# Charger_Control_Board_rev7.net
KiCad netlist of a schematic drawn in EAGLE
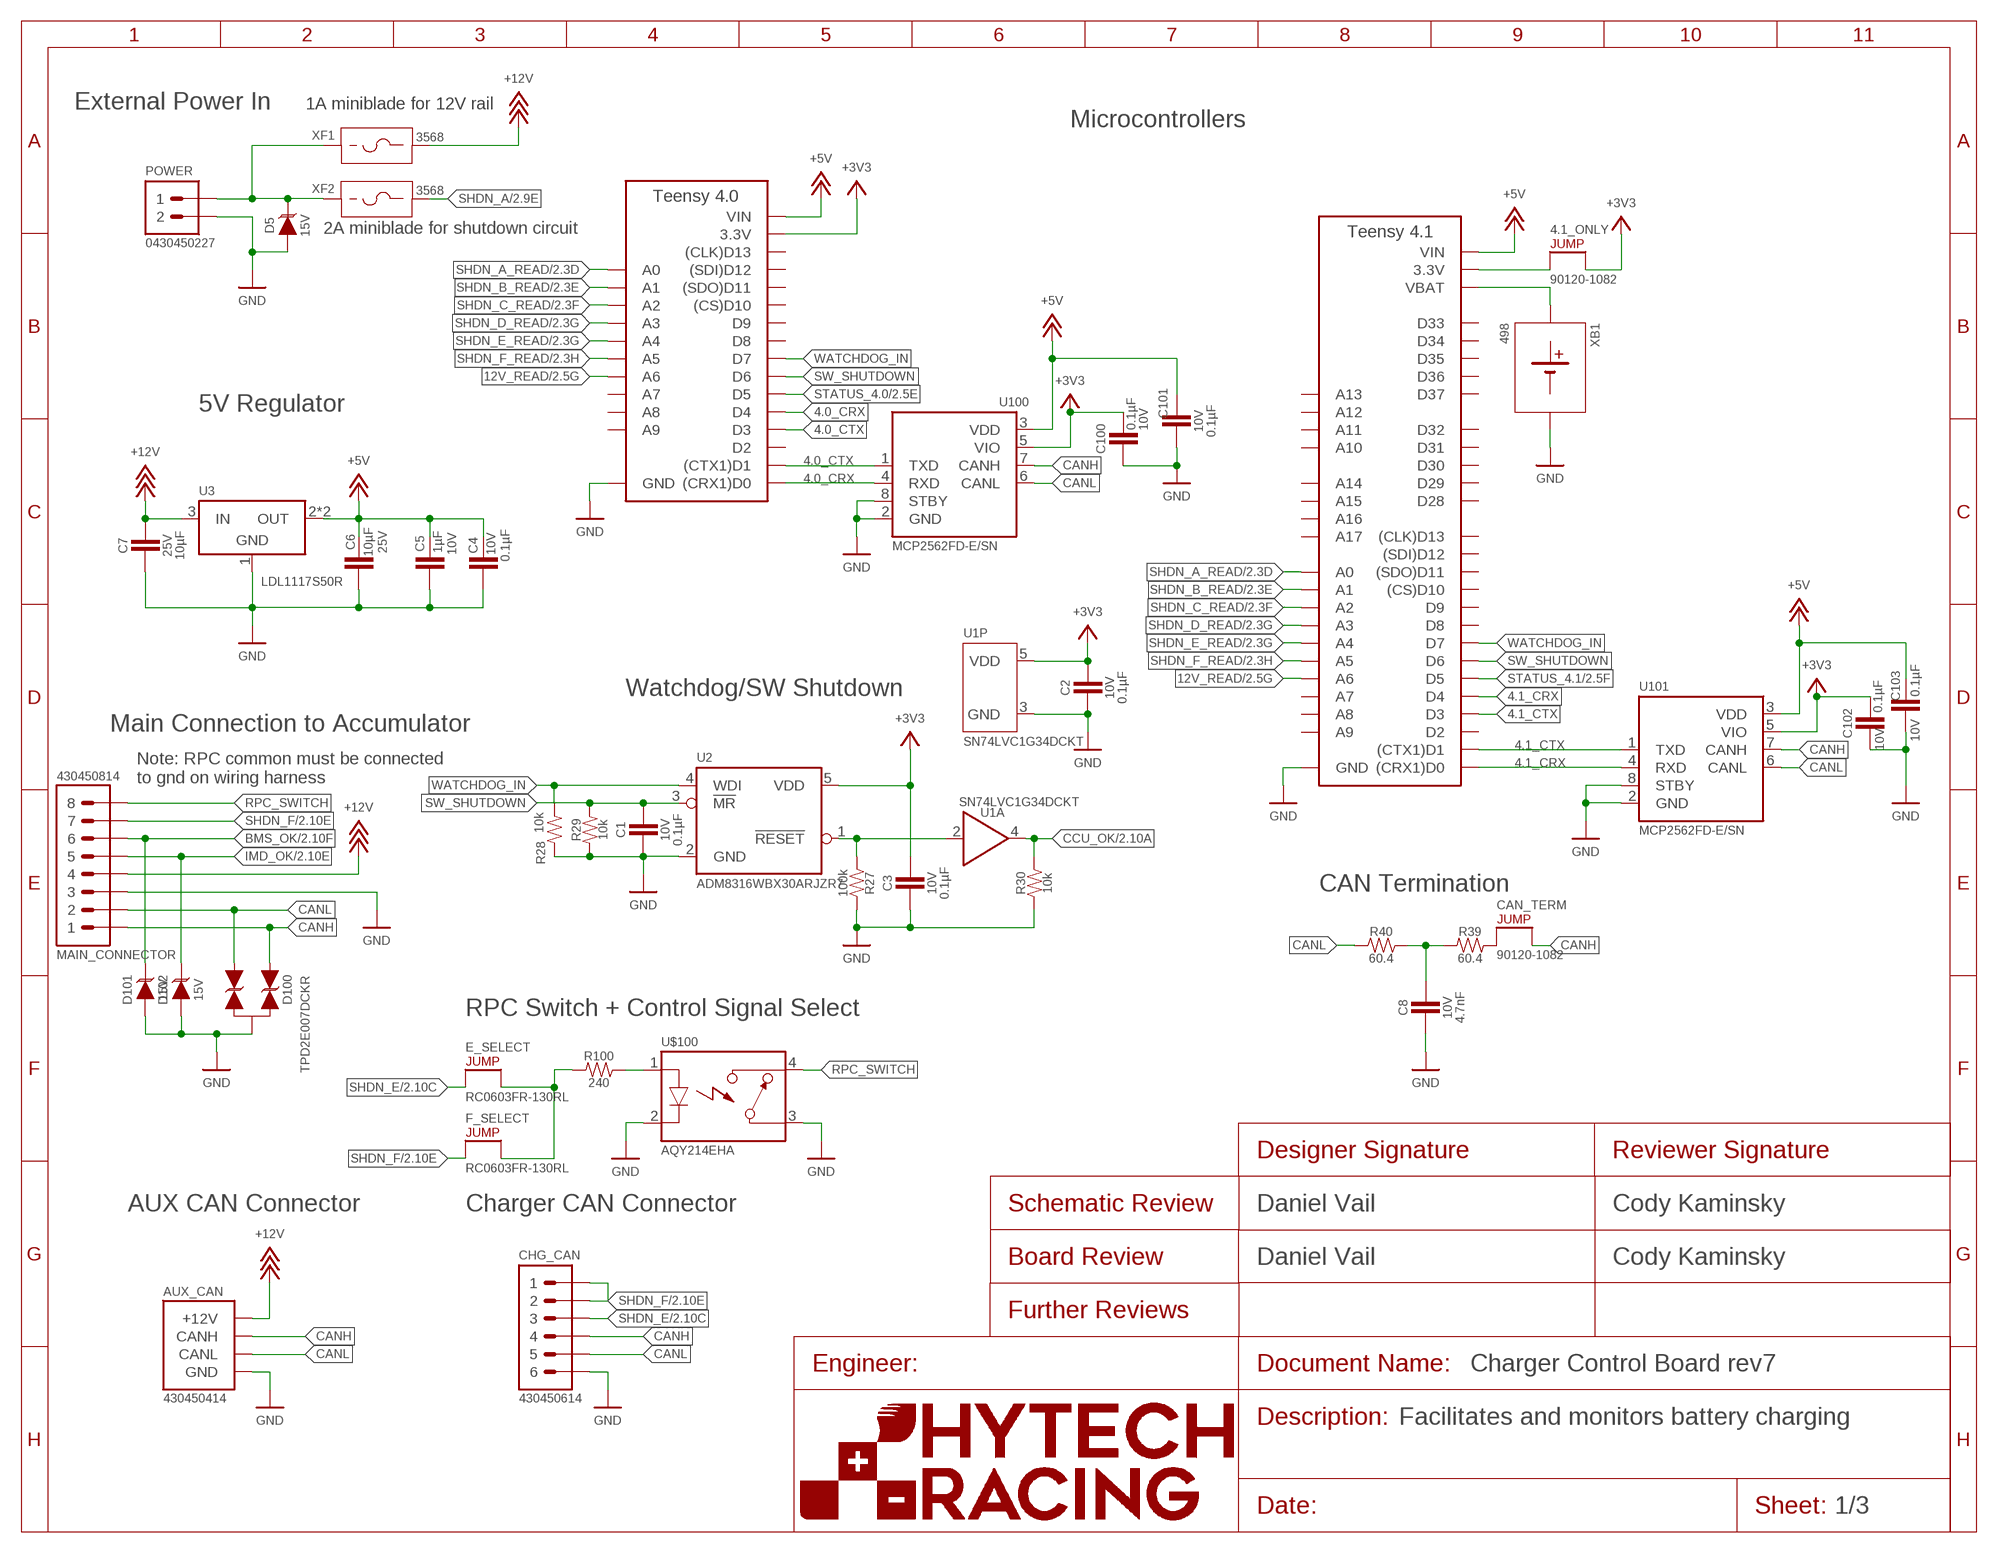
[diagram p0: schematic, sheet 1]
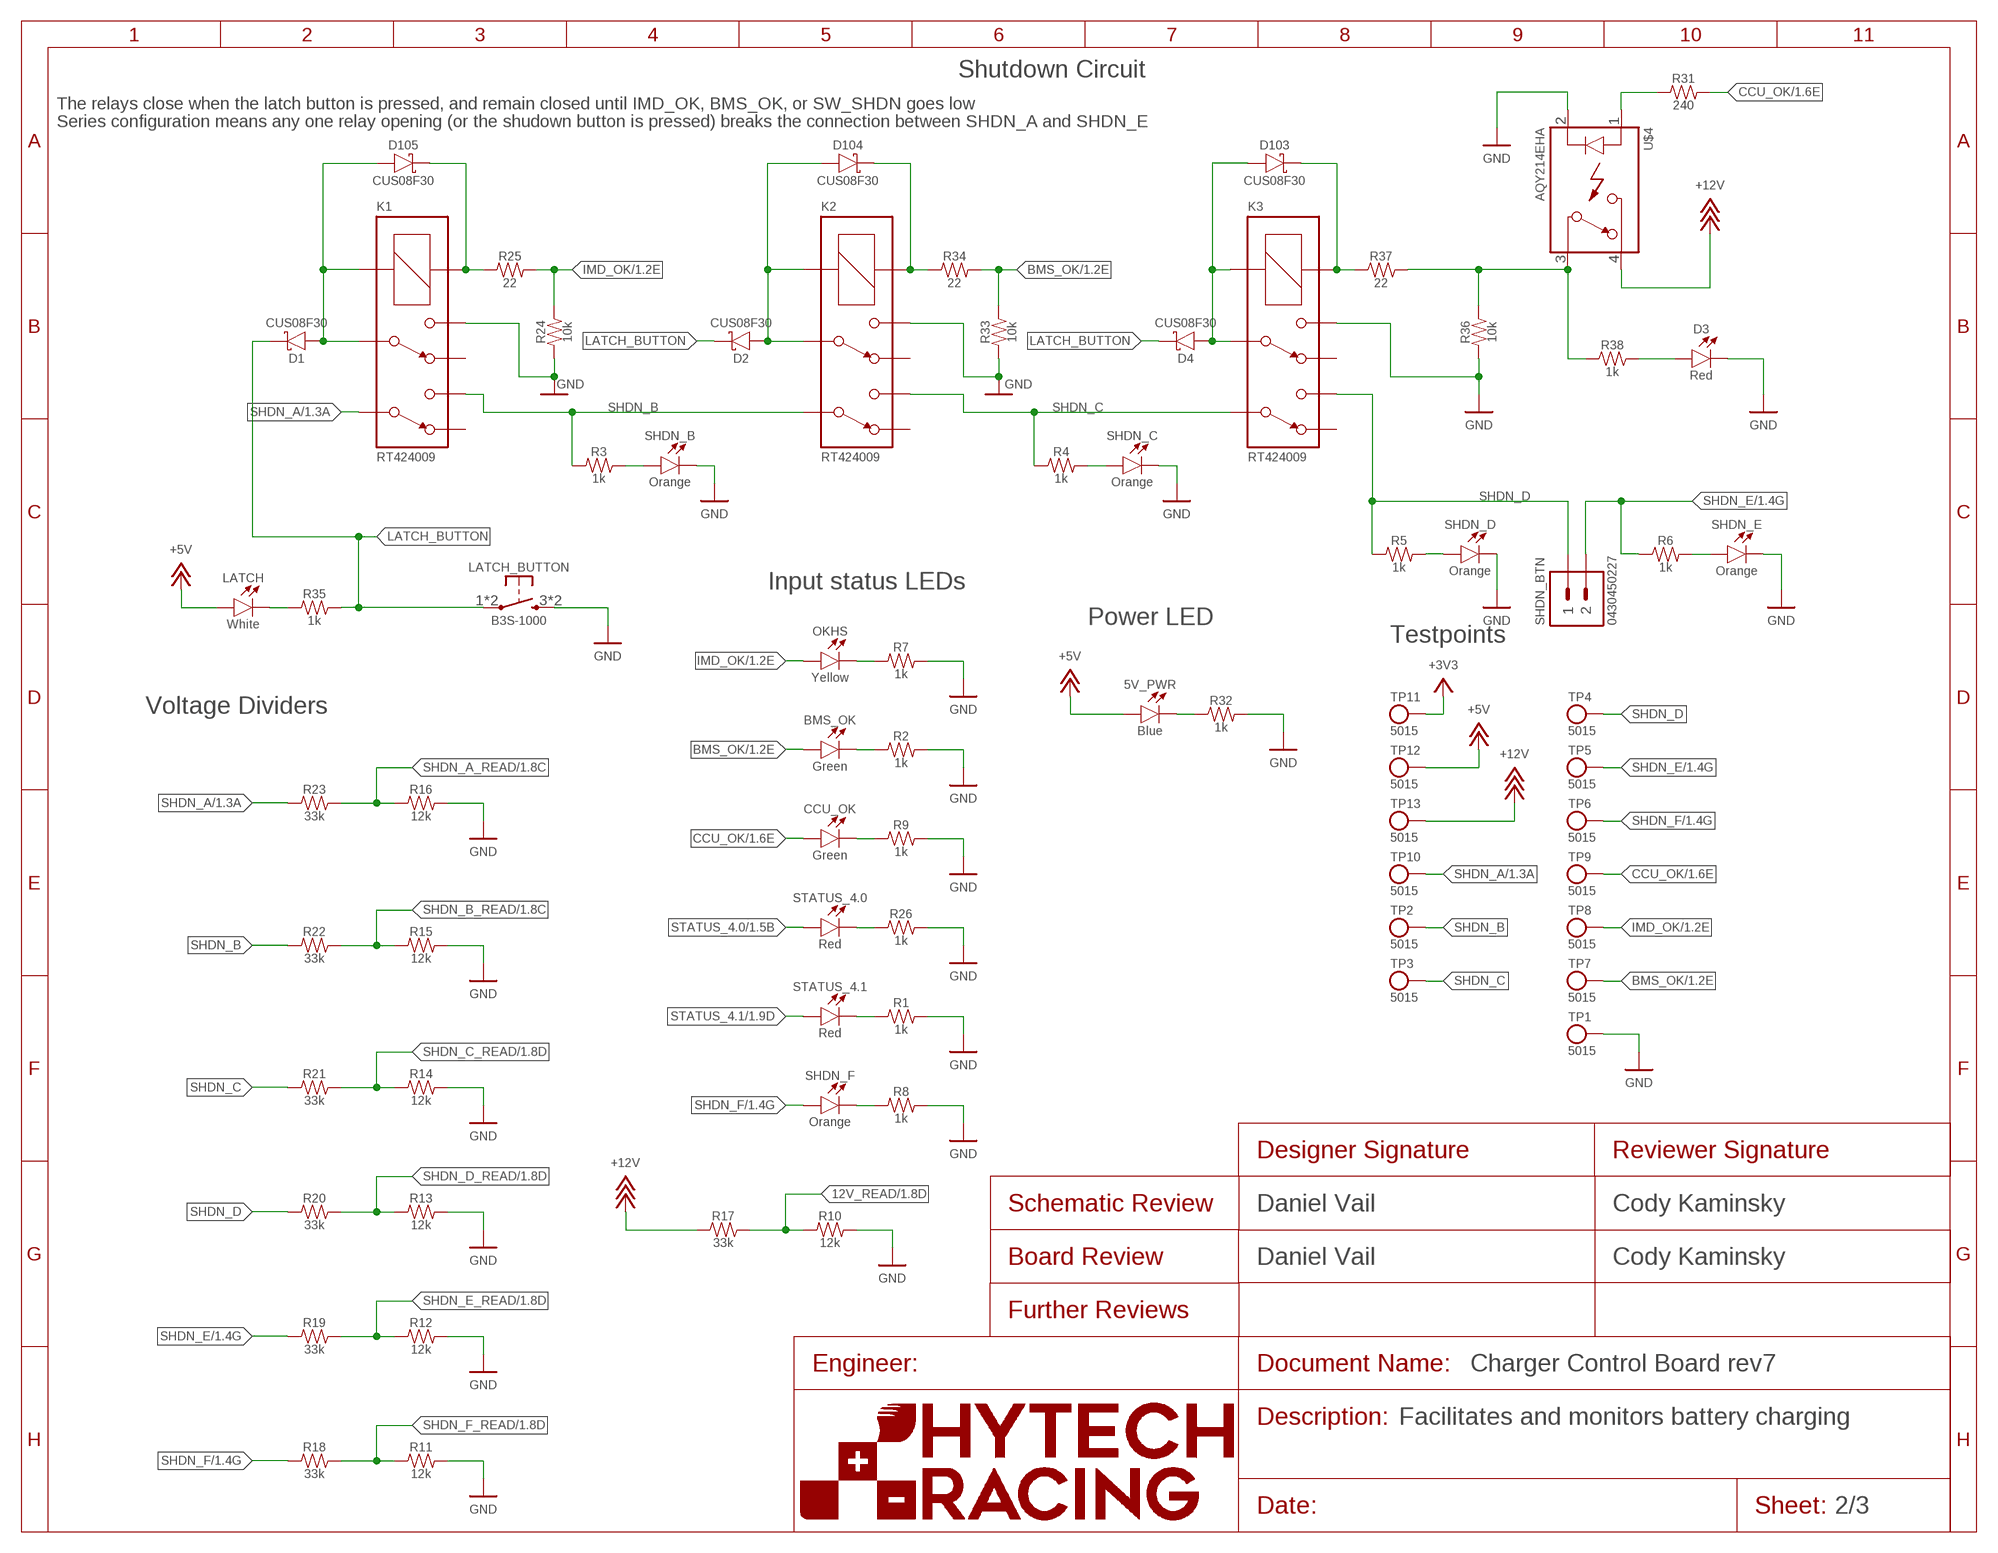
[diagram p1: schematic, sheet 2]
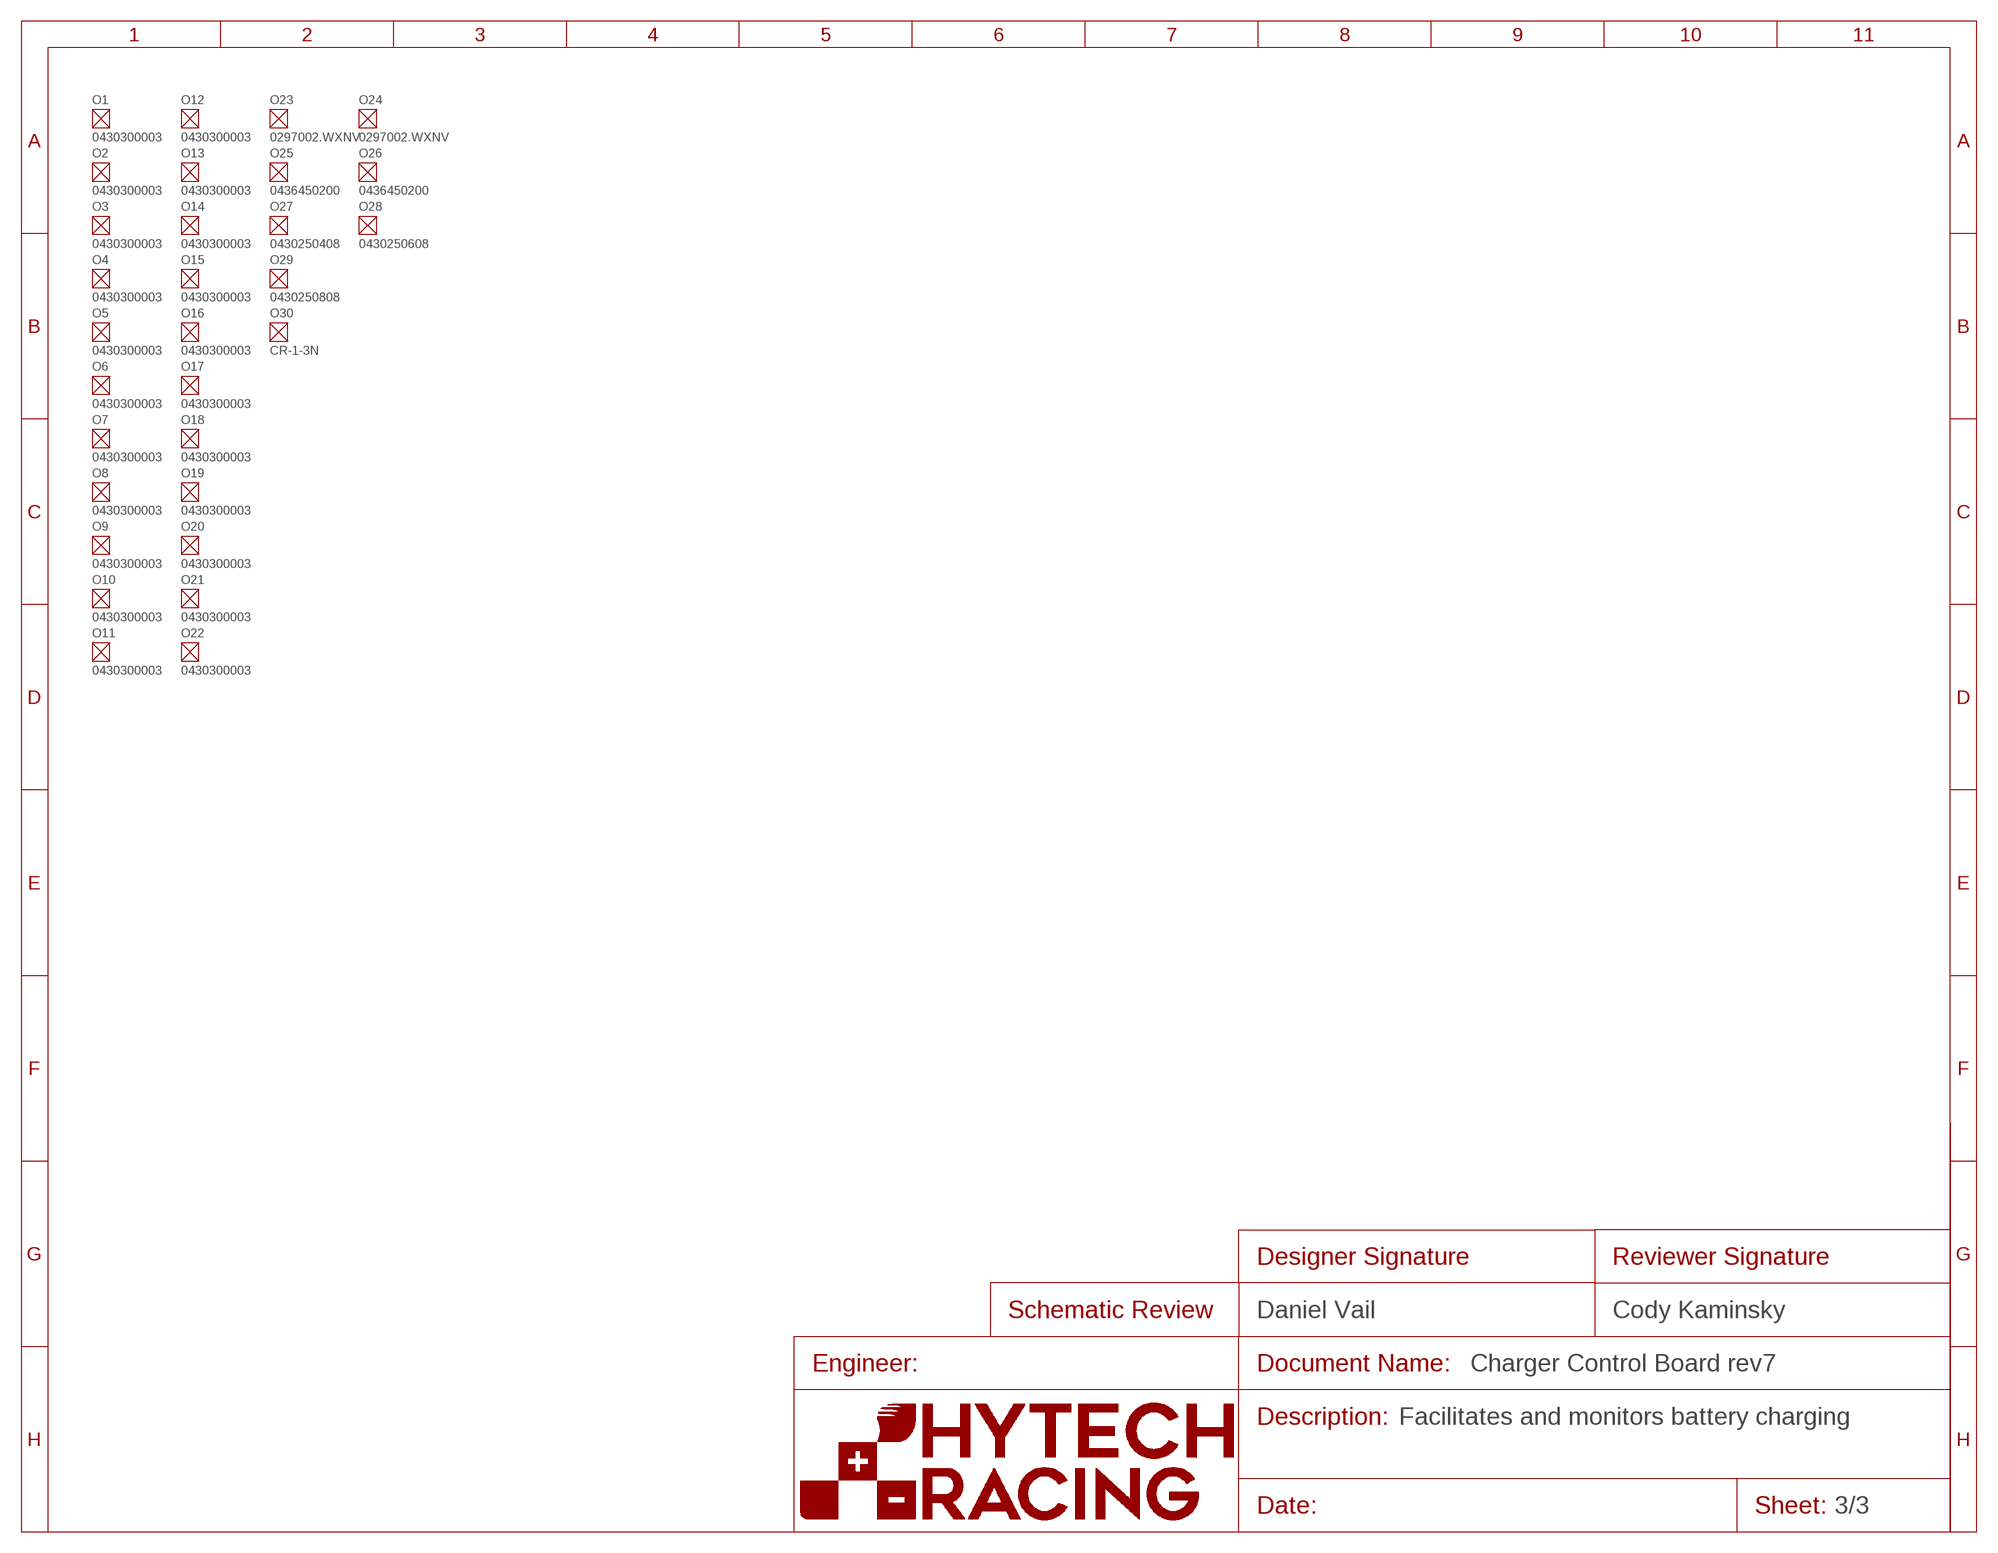
[diagram p2: schematic, sheet 3]

(export (version "E")
  (design (tool "Eeschema 10.0.6"))
  (components
    (comp (ref "5V_PWR")
      (value "LED_0603_BLUE")
      (footprint "eagle-import:0603-LED")
      (fields
        (field (name "COLOR") "Blue")
        (field (name "MANUFACTURER") "Kingbright")
        (field (name "MPN") "APT1608VBC/D")
      )
      (libsource (lib "eagle-import") (part "LED_?_0603BLUE"))
    )
    (comp (ref "BMS_OK")
      (value "LED_0603_GREEN")
      (footprint "eagle-import:0603-LED")
      (fields
        (field (name "COLOR") "Green")
        (field (name "MANUFACTURER") "Kingbright")
        (field (name "MPN") "APT1608ZGCK")
      )
      (libsource (lib "eagle-import") (part "LED_?_0603GREEN"))
    )
    (comp (ref "CCU_OK")
      (value "LED_0603_GREEN")
      (footprint "eagle-import:0603-LED")
      (fields
        (field (name "COLOR") "Green")
        (field (name "MANUFACTURER") "Kingbright")
        (field (name "MPN") "APT1608ZGCK")
      )
      (libsource (lib "eagle-import") (part "LED_?_0603GREEN"))
    )
    (comp (ref "D1")
      (value "SCHOTTKY_SOD323_30V")
      (footprint "eagle-import:SOD-323")
      (fields
        (field (name "MANUFACTURER") "Toshiba Semiconductor and Storage")
        (field (name "MPN") "CUS08F30")
        (field (name "VOLTAGE") "30V")
      )
      (libsource (lib "eagle-import") (part "SCHOTTKY_?_SOD32330V"))
    )
    (comp (ref "D2")
      (value "SCHOTTKY_SOD323_30V")
      (footprint "eagle-import:SOD-323")
      (fields
        (field (name "MANUFACTURER") "Toshiba Semiconductor and Storage")
        (field (name "MPN") "CUS08F30")
        (field (name "VOLTAGE") "30V")
      )
      (libsource (lib "eagle-import") (part "SCHOTTKY_?_SOD32330V"))
    )
    (comp (ref "D3")
      (value "LED_0603_RED")
      (footprint "eagle-import:0603-LED")
      (fields
        (field (name "COLOR") "Red")
        (field (name "MANUFACTURER") "Kingbright")
        (field (name "MPN") "APT1608SECK/J3-PRV")
      )
      (libsource (lib "eagle-import") (part "LED_?_0603RED"))
    )
    (comp (ref "D4")
      (value "SCHOTTKY_SOD323_30V")
      (footprint "eagle-import:SOD-323")
      (fields
        (field (name "MANUFACTURER") "Toshiba Semiconductor and Storage")
        (field (name "MPN") "CUS08F30")
        (field (name "VOLTAGE") "30V")
      )
      (libsource (lib "eagle-import") (part "SCHOTTKY_?_SOD32330V"))
    )
    (comp (ref "D103")
      (value "SCHOTTKY_SOD323_30V")
      (footprint "eagle-import:SOD-323")
      (fields
        (field (name "MANUFACTURER") "Toshiba Semiconductor and Storage")
        (field (name "MPN") "CUS08F30")
        (field (name "VOLTAGE") "30V")
      )
      (libsource (lib "eagle-import") (part "SCHOTTKY_?_SOD32330V"))
    )
    (comp (ref "D104")
      (value "SCHOTTKY_SOD323_30V")
      (footprint "eagle-import:SOD-323")
      (fields
        (field (name "MANUFACTURER") "Toshiba Semiconductor and Storage")
        (field (name "MPN") "CUS08F30")
        (field (name "VOLTAGE") "30V")
      )
      (libsource (lib "eagle-import") (part "SCHOTTKY_?_SOD32330V"))
    )
    (comp (ref "D105")
      (value "SCHOTTKY_SOD323_30V")
      (footprint "eagle-import:SOD-323")
      (fields
        (field (name "MANUFACTURER") "Toshiba Semiconductor and Storage")
        (field (name "MPN") "CUS08F30")
        (field (name "VOLTAGE") "30V")
      )
      (libsource (lib "eagle-import") (part "SCHOTTKY_?_SOD32330V"))
    )
    (comp (ref "K1")
      (value "RELAY_DPDT")
      (footprint "eagle-import:RT_2_")
      (fields (field (name "MPN") "RT424009") (field (name "MANUFACTURER") "TE Connectivity"))
      (libsource (lib "eagle-import") (part "RELAY_DPDT"))
    )
    (comp (ref "K2")
      (value "RELAY_DPDT")
      (footprint "eagle-import:RT_2_")
      (fields (field (name "MPN") "RT424009") (field (name "MANUFACTURER") "TE Connectivity"))
      (libsource (lib "eagle-import") (part "RELAY_DPDT"))
    )
    (comp (ref "K3")
      (value "RELAY_DPDT")
      (footprint "eagle-import:RT_2_")
      (fields (field (name "MPN") "RT424009") (field (name "MANUFACTURER") "TE Connectivity"))
      (libsource (lib "eagle-import") (part "RELAY_DPDT"))
    )
    (comp (ref "LATCH")
      (value "LED_0603_WHITE")
      (footprint "eagle-import:0603-LED")
      (fields
        (field (name "COLOR") "White")
        (field (name "MANUFACTURER") "Bivar Inc.")
        (field (name "MPN") "SM0603UWC")
      )
      (libsource (lib "eagle-import") (part "LED_?_0603WHITE"))
    )
    (comp (ref "LATCH_BUTTON")
      (value "BUTTON")
      (footprint "eagle-import:B3S-100X")
      (fields (field (name "MPN") "B3S-1000") (field (name "MANUFACTURER") "Omron"))
      (libsource (lib "eagle-import") (part "BUTTON"))
    )
    (comp (ref "OKHS")
      (value "LED_0603_YELLOW")
      (footprint "eagle-import:0603-LED")
      (fields
        (field (name "COLOR") "Yellow")
        (field (name "MANUFACTURER") "Kingbright")
        (field (name "MPN") "APT1608SYCK/J3-PRV")
      )
      (libsource (lib "eagle-import") (part "LED_?_0603YELLOW"))
    )
    (comp (ref "R1")
      (value "RESISTOR_0603_1K")
      (footprint "eagle-import:0603-RES")
      (fields
        (field (name "MANUFACTURER") "Yageo")
        (field (name "MPN") "RC0603FR-071KL")
        (field (name "POWER") "0.1W")
        (field (name "RESISTANCE") "1k")
      )
      (libsource (lib "eagle-import") (part "RESISTOR_?_06031K"))
    )
    (comp (ref "R2")
      (value "RESISTOR_0603_1K")
      (footprint "eagle-import:0603-RES")
      (fields
        (field (name "MANUFACTURER") "Yageo")
        (field (name "MPN") "RC0603FR-071KL")
        (field (name "POWER") "0.1W")
        (field (name "RESISTANCE") "1k")
      )
      (libsource (lib "eagle-import") (part "RESISTOR_?_06031K"))
    )
    (comp (ref "R3")
      (value "RESISTOR_0603_1K")
      (footprint "eagle-import:0603-RES")
      (fields
        (field (name "MANUFACTURER") "Yageo")
        (field (name "MPN") "RC0603FR-071KL")
        (field (name "POWER") "0.1W")
        (field (name "RESISTANCE") "1k")
      )
      (libsource (lib "eagle-import") (part "RESISTOR_?_06031K"))
    )
    (comp (ref "R4")
      (value "RESISTOR_0603_1K")
      (footprint "eagle-import:0603-RES")
      (fields
        (field (name "MANUFACTURER") "Yageo")
        (field (name "MPN") "RC0603FR-071KL")
        (field (name "POWER") "0.1W")
        (field (name "RESISTANCE") "1k")
      )
      (libsource (lib "eagle-import") (part "RESISTOR_?_06031K"))
    )
    (comp (ref "R5")
      (value "RESISTOR_0603_1K")
      (footprint "eagle-import:0603-RES")
      (fields
        (field (name "MANUFACTURER") "Yageo")
        (field (name "MPN") "RC0603FR-071KL")
        (field (name "POWER") "0.1W")
        (field (name "RESISTANCE") "1k")
      )
      (libsource (lib "eagle-import") (part "RESISTOR_?_06031K"))
    )
    (comp (ref "R6")
      (value "RESISTOR_0603_1K")
      (footprint "eagle-import:0603-RES")
      (fields
        (field (name "MANUFACTURER") "Yageo")
        (field (name "MPN") "RC0603FR-071KL")
        (field (name "POWER") "0.1W")
        (field (name "RESISTANCE") "1k")
      )
      (libsource (lib "eagle-import") (part "RESISTOR_?_06031K"))
    )
    (comp (ref "R7")
      (value "RESISTOR_0603_1K")
      (footprint "eagle-import:0603-RES")
      (fields
        (field (name "MANUFACTURER") "Yageo")
        (field (name "MPN") "RC0603FR-071KL")
        (field (name "POWER") "0.1W")
        (field (name "RESISTANCE") "1k")
      )
      (libsource (lib "eagle-import") (part "RESISTOR_?_06031K"))
    )
    (comp (ref "R8")
      (value "RESISTOR_0603_1K")
      (footprint "eagle-import:0603-RES")
      (fields
        (field (name "MANUFACTURER") "Yageo")
        (field (name "MPN") "RC0603FR-071KL")
        (field (name "POWER") "0.1W")
        (field (name "RESISTANCE") "1k")
      )
      (libsource (lib "eagle-import") (part "RESISTOR_?_06031K"))
    )
    (comp (ref "R9")
      (value "RESISTOR_0603_1K")
      (footprint "eagle-import:0603-RES")
      (fields
        (field (name "MANUFACTURER") "Yageo")
        (field (name "MPN") "RC0603FR-071KL")
        (field (name "POWER") "0.1W")
        (field (name "RESISTANCE") "1k")
      )
      (libsource (lib "eagle-import") (part "RESISTOR_?_06031K"))
    )
    (comp (ref "R10")
      (value "RESISTOR_0603_12K")
      (footprint "eagle-import:0603-RES")
      (fields
        (field (name "MANUFACTURER") "Yageo")
        (field (name "MPN") "RC0603FR-0712KL")
        (field (name "POWER") "0.1W")
        (field (name "RESISTANCE") "12k")
      )
      (libsource (lib "eagle-import") (part "RESISTOR_?_060312K"))
    )
    (comp (ref "R11")
      (value "RESISTOR_0603_12K")
      (footprint "eagle-import:0603-RES")
      (fields
        (field (name "MANUFACTURER") "Yageo")
        (field (name "MPN") "RC0603FR-0712KL")
        (field (name "POWER") "0.1W")
        (field (name "RESISTANCE") "12k")
      )
      (libsource (lib "eagle-import") (part "RESISTOR_?_060312K"))
    )
    (comp (ref "R12")
      (value "RESISTOR_0603_12K")
      (footprint "eagle-import:0603-RES")
      (fields
        (field (name "MANUFACTURER") "Yageo")
        (field (name "MPN") "RC0603FR-0712KL")
        (field (name "POWER") "0.1W")
        (field (name "RESISTANCE") "12k")
      )
      (libsource (lib "eagle-import") (part "RESISTOR_?_060312K"))
    )
    (comp (ref "R13")
      (value "RESISTOR_0603_12K")
      (footprint "eagle-import:0603-RES")
      (fields
        (field (name "MANUFACTURER") "Yageo")
        (field (name "MPN") "RC0603FR-0712KL")
        (field (name "POWER") "0.1W")
        (field (name "RESISTANCE") "12k")
      )
      (libsource (lib "eagle-import") (part "RESISTOR_?_060312K"))
    )
    (comp (ref "R14")
      (value "RESISTOR_0603_12K")
      (footprint "eagle-import:0603-RES")
      (fields
        (field (name "MANUFACTURER") "Yageo")
        (field (name "MPN") "RC0603FR-0712KL")
        (field (name "POWER") "0.1W")
        (field (name "RESISTANCE") "12k")
      )
      (libsource (lib "eagle-import") (part "RESISTOR_?_060312K"))
    )
    (comp (ref "R15")
      (value "RESISTOR_0603_12K")
      (footprint "eagle-import:0603-RES")
      (fields
        (field (name "MANUFACTURER") "Yageo")
        (field (name "MPN") "RC0603FR-0712KL")
        (field (name "POWER") "0.1W")
        (field (name "RESISTANCE") "12k")
      )
      (libsource (lib "eagle-import") (part "RESISTOR_?_060312K"))
    )
    (comp (ref "R16")
      (value "RESISTOR_0603_12K")
      (footprint "eagle-import:0603-RES")
      (fields
        (field (name "MANUFACTURER") "Yageo")
        (field (name "MPN") "RC0603FR-0712KL")
        (field (name "POWER") "0.1W")
        (field (name "RESISTANCE") "12k")
      )
      (libsource (lib "eagle-import") (part "RESISTOR_?_060312K"))
    )
    (comp (ref "R17")
      (value "RESISTOR_0603_33K")
      (footprint "eagle-import:0603-RES")
      (fields
        (field (name "MANUFACTURER") "Rohm Semiconductor")
        (field (name "MPN") "KTR03EZPF3302")
        (field (name "POWER") "0.1W")
        (field (name "RESISTANCE") "33k")
      )
      (libsource (lib "eagle-import") (part "RESISTOR_?_060333K"))
    )
    (comp (ref "R18")
      (value "RESISTOR_0603_33K")
      (footprint "eagle-import:0603-RES")
      (fields
        (field (name "MANUFACTURER") "Rohm Semiconductor")
        (field (name "MPN") "KTR03EZPF3302")
        (field (name "POWER") "0.1W")
        (field (name "RESISTANCE") "33k")
      )
      (libsource (lib "eagle-import") (part "RESISTOR_?_060333K"))
    )
    (comp (ref "R19")
      (value "RESISTOR_0603_33K")
      (footprint "eagle-import:0603-RES")
      (fields
        (field (name "MANUFACTURER") "Rohm Semiconductor")
        (field (name "MPN") "KTR03EZPF3302")
        (field (name "POWER") "0.1W")
        (field (name "RESISTANCE") "33k")
      )
      (libsource (lib "eagle-import") (part "RESISTOR_?_060333K"))
    )
    (comp (ref "R20")
      (value "RESISTOR_0603_33K")
      (footprint "eagle-import:0603-RES")
      (fields
        (field (name "MANUFACTURER") "Rohm Semiconductor")
        (field (name "MPN") "KTR03EZPF3302")
        (field (name "POWER") "0.1W")
        (field (name "RESISTANCE") "33k")
      )
      (libsource (lib "eagle-import") (part "RESISTOR_?_060333K"))
    )
    (comp (ref "R21")
      (value "RESISTOR_0603_33K")
      (footprint "eagle-import:0603-RES")
      (fields
        (field (name "MANUFACTURER") "Rohm Semiconductor")
        (field (name "MPN") "KTR03EZPF3302")
        (field (name "POWER") "0.1W")
        (field (name "RESISTANCE") "33k")
      )
      (libsource (lib "eagle-import") (part "RESISTOR_?_060333K"))
    )
    (comp (ref "R22")
      (value "RESISTOR_0603_33K")
      (footprint "eagle-import:0603-RES")
      (fields
        (field (name "MANUFACTURER") "Rohm Semiconductor")
        (field (name "MPN") "KTR03EZPF3302")
        (field (name "POWER") "0.1W")
        (field (name "RESISTANCE") "33k")
      )
      (libsource (lib "eagle-import") (part "RESISTOR_?_060333K"))
    )
    (comp (ref "R23")
      (value "RESISTOR_0603_33K")
      (footprint "eagle-import:0603-RES")
      (fields
        (field (name "MANUFACTURER") "Rohm Semiconductor")
        (field (name "MPN") "KTR03EZPF3302")
        (field (name "POWER") "0.1W")
        (field (name "RESISTANCE") "33k")
      )
      (libsource (lib "eagle-import") (part "RESISTOR_?_060333K"))
    )
    (comp (ref "R24")
      (value "RESISTOR_0603_10K")
      (footprint "eagle-import:0603-RES")
      (fields
        (field (name "MANUFACTURER") "Yageo")
        (field (name "MPN") "RC0603FR-0710KL")
        (field (name "POWER") "0.1W")
        (field (name "RESISTANCE") "10k")
      )
      (libsource (lib "eagle-import") (part "RESISTOR_?_060310K"))
    )
    (comp (ref "R25")
      (value "RESISTOR_0603_22")
      (footprint "eagle-import:0603-RES")
      (fields
        (field (name "MANUFACTURER") "Yageo")
        (field (name "MPN") "RC0603FR-0722RL")
        (field (name "POWER") "0.1W")
        (field (name "RESISTANCE") "22")
      )
      (libsource (lib "eagle-import") (part "RESISTOR_?_060322"))
    )
    (comp (ref "R26")
      (value "RESISTOR_0603_1K")
      (footprint "eagle-import:0603-RES")
      (fields
        (field (name "MANUFACTURER") "Yageo")
        (field (name "MPN") "RC0603FR-071KL")
        (field (name "POWER") "0.1W")
        (field (name "RESISTANCE") "1k")
      )
      (libsource (lib "eagle-import") (part "RESISTOR_?_06031K"))
    )
    (comp (ref "R31")
      (value "RESISTOR_0603_240")
      (footprint "eagle-import:0603-RES")
      (fields
        (field (name "MANUFACTURER") "Yageo")
        (field (name "MPN") "RC0603FR-07240RL")
        (field (name "POWER") "0.1W")
        (field (name "RESISTANCE") "240")
      )
      (libsource (lib "eagle-import") (part "RESISTOR_?_0603240"))
    )
    (comp (ref "R32")
      (value "RESISTOR_0603_1K")
      (footprint "eagle-import:0603-RES")
      (fields
        (field (name "MANUFACTURER") "Yageo")
        (field (name "MPN") "RC0603FR-071KL")
        (field (name "POWER") "0.1W")
        (field (name "RESISTANCE") "1k")
      )
      (libsource (lib "eagle-import") (part "RESISTOR_?_06031K"))
    )
    (comp (ref "R33")
      (value "RESISTOR_0603_10K")
      (footprint "eagle-import:0603-RES")
      (fields
        (field (name "MANUFACTURER") "Yageo")
        (field (name "MPN") "RC0603FR-0710KL")
        (field (name "POWER") "0.1W")
        (field (name "RESISTANCE") "10k")
      )
      (libsource (lib "eagle-import") (part "RESISTOR_?_060310K"))
    )
    (comp (ref "R34")
      (value "RESISTOR_0603_22")
      (footprint "eagle-import:0603-RES")
      (fields
        (field (name "MANUFACTURER") "Yageo")
        (field (name "MPN") "RC0603FR-0722RL")
        (field (name "POWER") "0.1W")
        (field (name "RESISTANCE") "22")
      )
      (libsource (lib "eagle-import") (part "RESISTOR_?_060322"))
    )
    (comp (ref "R35")
      (value "RESISTOR_0603_1K")
      (footprint "eagle-import:0603-RES")
      (fields
        (field (name "MANUFACTURER") "Yageo")
        (field (name "MPN") "RC0603FR-071KL")
        (field (name "POWER") "0.1W")
        (field (name "RESISTANCE") "1k")
      )
      (libsource (lib "eagle-import") (part "RESISTOR_?_06031K"))
    )
    (comp (ref "R36")
      (value "RESISTOR_0603_10K")
      (footprint "eagle-import:0603-RES")
      (fields
        (field (name "MANUFACTURER") "Yageo")
        (field (name "MPN") "RC0603FR-0710KL")
        (field (name "POWER") "0.1W")
        (field (name "RESISTANCE") "10k")
      )
      (libsource (lib "eagle-import") (part "RESISTOR_?_060310K"))
    )
    (comp (ref "R37")
      (value "RESISTOR_0603_22")
      (footprint "eagle-import:0603-RES")
      (fields
        (field (name "MANUFACTURER") "Yageo")
        (field (name "MPN") "RC0603FR-0722RL")
        (field (name "POWER") "0.1W")
        (field (name "RESISTANCE") "22")
      )
      (libsource (lib "eagle-import") (part "RESISTOR_?_060322"))
    )
    (comp (ref "R38")
      (value "RESISTOR_0603_1K")
      (footprint "eagle-import:0603-RES")
      (fields
        (field (name "MANUFACTURER") "Yageo")
        (field (name "MPN") "RC0603FR-071KL")
        (field (name "POWER") "0.1W")
        (field (name "RESISTANCE") "1k")
      )
      (libsource (lib "eagle-import") (part "RESISTOR_?_06031K"))
    )
    (comp (ref "SHDN_B")
      (value "LED_0603_ORANGE")
      (footprint "eagle-import:0603-LED")
      (fields
        (field (name "COLOR") "Orange")
        (field (name "MANUFACTURER") "Kingbright")
        (field (name "MPN") "APT1608SECK")
      )
      (libsource (lib "eagle-import") (part "LED_?_0603ORANGE"))
    )
    (comp (ref "SHDN_BTN")
      (value "CONNECTOR-2_μF_T_V_")
      (footprint "eagle-import:MOLEX_MICROFIT_PTH_VERTICAL_02_DUAL")
      (fields (field (name "MPN") "0430450227") (field (name "MANUFACTURER") "Molex"))
      (libsource (lib "eagle-import") (part "CONNECTOR-2_?_μF_T_V"))
    )
    (comp (ref "SHDN_C")
      (value "LED_0603_ORANGE")
      (footprint "eagle-import:0603-LED")
      (fields
        (field (name "COLOR") "Orange")
        (field (name "MANUFACTURER") "Kingbright")
        (field (name "MPN") "APT1608SECK")
      )
      (libsource (lib "eagle-import") (part "LED_?_0603ORANGE"))
    )
    (comp (ref "SHDN_D")
      (value "LED_0603_ORANGE")
      (footprint "eagle-import:0603-LED")
      (fields
        (field (name "COLOR") "Orange")
        (field (name "MANUFACTURER") "Kingbright")
        (field (name "MPN") "APT1608SECK")
      )
      (libsource (lib "eagle-import") (part "LED_?_0603ORANGE"))
    )
    (comp (ref "SHDN_E")
      (value "LED_0603_ORANGE")
      (footprint "eagle-import:0603-LED")
      (fields
        (field (name "COLOR") "Orange")
        (field (name "MANUFACTURER") "Kingbright")
        (field (name "MPN") "APT1608SECK")
      )
      (libsource (lib "eagle-import") (part "LED_?_0603ORANGE"))
    )
    (comp (ref "SHDN_F")
      (value "LED_0603_ORANGE")
      (footprint "eagle-import:0603-LED")
      (fields
        (field (name "COLOR") "Orange")
        (field (name "MANUFACTURER") "Kingbright")
        (field (name "MPN") "APT1608SECK")
      )
      (libsource (lib "eagle-import") (part "LED_?_0603ORANGE"))
    )
    (comp (ref "STATUS_4.0")
      (value "LED_0603_RED")
      (footprint "eagle-import:0603-LED")
      (fields
        (field (name "COLOR") "Red")
        (field (name "MANUFACTURER") "Kingbright")
        (field (name "MPN") "APT1608SECK/J3-PRV")
      )
      (libsource (lib "eagle-import") (part "LED_?_0603RED"))
    )
    (comp (ref "STATUS_4.1")
      (value "LED_0603_RED")
      (footprint "eagle-import:0603-LED")
      (fields
        (field (name "COLOR") "Red")
        (field (name "MANUFACTURER") "Kingbright")
        (field (name "MPN") "APT1608SECK/J3-PRV")
      )
      (libsource (lib "eagle-import") (part "LED_?_0603RED"))
    )
    (comp (ref "TP1")
      (value "TEST_POINT")
      (footprint "eagle-import:5015")
      (fields (field (name "MPN") "5015") (field (name "MANUFACTURER") "Keystone Electronics"))
      (libsource (lib "eagle-import") (part "TEST_POINT"))
    )
    (comp (ref "TP2")
      (value "TEST_POINT")
      (footprint "eagle-import:5015")
      (fields (field (name "MPN") "5015") (field (name "MANUFACTURER") "Keystone Electronics"))
      (libsource (lib "eagle-import") (part "TEST_POINT"))
    )
    (comp (ref "TP3")
      (value "TEST_POINT")
      (footprint "eagle-import:5015")
      (fields (field (name "MPN") "5015") (field (name "MANUFACTURER") "Keystone Electronics"))
      (libsource (lib "eagle-import") (part "TEST_POINT"))
    )
    (comp (ref "TP4")
      (value "TEST_POINT")
      (footprint "eagle-import:5015")
      (fields (field (name "MPN") "5015") (field (name "MANUFACTURER") "Keystone Electronics"))
      (libsource (lib "eagle-import") (part "TEST_POINT"))
    )
    (comp (ref "TP5")
      (value "TEST_POINT")
      (footprint "eagle-import:5015")
      (fields (field (name "MPN") "5015") (field (name "MANUFACTURER") "Keystone Electronics"))
      (libsource (lib "eagle-import") (part "TEST_POINT"))
    )
    (comp (ref "TP6")
      (value "TEST_POINT")
      (footprint "eagle-import:5015")
      (fields (field (name "MPN") "5015") (field (name "MANUFACTURER") "Keystone Electronics"))
      (libsource (lib "eagle-import") (part "TEST_POINT"))
    )
    (comp (ref "TP7")
      (value "TEST_POINT")
      (footprint "eagle-import:5015")
      (fields (field (name "MPN") "5015") (field (name "MANUFACTURER") "Keystone Electronics"))
      (libsource (lib "eagle-import") (part "TEST_POINT"))
    )
    (comp (ref "TP8")
      (value "TEST_POINT")
      (footprint "eagle-import:5015")
      (fields (field (name "MPN") "5015") (field (name "MANUFACTURER") "Keystone Electronics"))
      (libsource (lib "eagle-import") (part "TEST_POINT"))
    )
    (comp (ref "TP9")
      (value "TEST_POINT")
      (footprint "eagle-import:5015")
      (fields (field (name "MPN") "5015") (field (name "MANUFACTURER") "Keystone Electronics"))
      (libsource (lib "eagle-import") (part "TEST_POINT"))
    )
    (comp (ref "TP10")
      (value "TEST_POINT")
      (footprint "eagle-import:5015")
      (fields (field (name "MPN") "5015") (field (name "MANUFACTURER") "Keystone Electronics"))
      (libsource (lib "eagle-import") (part "TEST_POINT"))
    )
    (comp (ref "TP11")
      (value "TEST_POINT")
      (footprint "eagle-import:5015")
      (fields (field (name "MPN") "5015") (field (name "MANUFACTURER") "Keystone Electronics"))
      (libsource (lib "eagle-import") (part "TEST_POINT"))
    )
    (comp (ref "TP12")
      (value "TEST_POINT")
      (footprint "eagle-import:5015")
      (fields (field (name "MPN") "5015") (field (name "MANUFACTURER") "Keystone Electronics"))
      (libsource (lib "eagle-import") (part "TEST_POINT"))
    )
    (comp (ref "TP13")
      (value "TEST_POINT")
      (footprint "eagle-import:5015")
      (fields (field (name "MPN") "5015") (field (name "MANUFACTURER") "Keystone Electronics"))
      (libsource (lib "eagle-import") (part "TEST_POINT"))
    )
    (comp (ref "U$4")
      (value "RELAY_SOLIDSTATE_NO")
      (footprint "eagle-import:DIP-4")
      (fields (field (name "MPN") "AQY214EHA") (field (name "MANUFACTURER") "AQY214EHA"))
      (libsource (lib "eagle-import") (part "RELAY_SOLIDSTATE_NO"))
    )
    (comp (ref "4.1_ONLY")
      (value "JUMPER__1X02")
      (footprint "eagle-import:1X02")
      (fields (field (name "MANUFACTURER") "Molex") (field (name "MPN") "90120-1082 "))
      (libsource (lib "eagle-import") (part "JUMPER_?_1X02"))
    )
    (comp (ref "A1")
      (value "TEENSY_4.1")
      (footprint "eagle-import:TEENSY_LONG_EXT")
      (libsource (lib "eagle-import") (part "TEENSY_4.1"))
    )
    (comp (ref "A2")
      (value "TEENSY_4.0")
      (footprint "eagle-import:TEENSY_SHORT")
      (libsource (lib "eagle-import") (part "TEENSY_4.0"))
    )
    (comp (ref "AUX_CAN")
      (value "CONNECTOR-CAN_MF_T_V_")
      (footprint "eagle-import:MOLEX_MICROFIT_PTH_VERTICAL_04_DUAL")
      (fields (field (name "MPN") "430450414") (field (name "MANUFACTURER") "Molex"))
      (libsource (lib "eagle-import") (part "CONNECTOR-CAN_?_MF_T_V"))
    )
    (comp (ref "C1")
      (value "CAPACITOR_0603_10V_0.1UF")
      (footprint "eagle-import:0603-CAP")
      (fields
        (field (name "CAPACITANCE") "0.1µF")
        (field (name "MANUFACTURER") "Vishay Vitramon")
        (field (name "MPN") "VJ0603Y104JXQPW1BC")
        (field (name "TOLERANCE") "5%")
        (field (name "VOLTAGE") "10V")
      )
      (libsource (lib "eagle-import") (part "CAPACITOR_?_060310V_0.1UF"))
    )
    (comp (ref "C2")
      (value "CAPACITOR_0603_10V_0.1UF")
      (footprint "eagle-import:0603-CAP")
      (fields
        (field (name "CAPACITANCE") "0.1µF")
        (field (name "MANUFACTURER") "Vishay Vitramon")
        (field (name "MPN") "VJ0603Y104JXQPW1BC")
        (field (name "TOLERANCE") "5%")
        (field (name "VOLTAGE") "10V")
      )
      (libsource (lib "eagle-import") (part "CAPACITOR_?_060310V_0.1UF"))
    )
    (comp (ref "C3")
      (value "CAPACITOR_0603_10V_0.1UF")
      (footprint "eagle-import:0603-CAP")
      (fields
        (field (name "CAPACITANCE") "0.1µF")
        (field (name "MANUFACTURER") "Vishay Vitramon")
        (field (name "MPN") "VJ0603Y104JXQPW1BC")
        (field (name "TOLERANCE") "5%")
        (field (name "VOLTAGE") "10V")
      )
      (libsource (lib "eagle-import") (part "CAPACITOR_?_060310V_0.1UF"))
    )
    (comp (ref "C4")
      (value "CAPACITOR_0603_10V_0.1UF")
      (footprint "eagle-import:0603-CAP")
      (fields
        (field (name "CAPACITANCE") "0.1µF")
        (field (name "MANUFACTURER") "Vishay Vitramon")
        (field (name "MPN") "VJ0603Y104JXQPW1BC")
        (field (name "TOLERANCE") "5%")
        (field (name "VOLTAGE") "10V")
      )
      (libsource (lib "eagle-import") (part "CAPACITOR_?_060310V_0.1UF"))
    )
    (comp (ref "C5")
      (value "CAPACITOR_0603_10V_1UF")
      (footprint "eagle-import:0603-CAP")
      (fields
        (field (name "CAPACITANCE") "1µF")
        (field (name "MANUFACTURER") "Yageo")
        (field (name "MPN") "CC0603KRX7R6BB105")
        (field (name "TOLERANCE") "10%")
        (field (name "VOLTAGE") "10V")
      )
      (libsource (lib "eagle-import") (part "CAPACITOR_?_060310V_1UF"))
    )
    (comp (ref "C6")
      (value "CAPACITOR_0603_25V_10UF")
      (footprint "eagle-import:0603-CAP")
      (fields
        (field (name "CAPACITANCE") "10µF")
        (field (name "MANUFACTURER") "Murata Electronics")
        (field (name "MPN") "GRM188R61E106MA73D")
        (field (name "TOLERANCE") "20%")
        (field (name "VOLTAGE") "25V")
      )
      (libsource (lib "eagle-import") (part "CAPACITOR_?_060325V_10UF"))
    )
    (comp (ref "C7")
      (value "CAPACITOR_0603_25V_10UF")
      (footprint "eagle-import:0603-CAP")
      (fields
        (field (name "CAPACITANCE") "10µF")
        (field (name "MANUFACTURER") "Murata Electronics")
        (field (name "MPN") "GRM188R61E106MA73D")
        (field (name "TOLERANCE") "20%")
        (field (name "VOLTAGE") "25V")
      )
      (libsource (lib "eagle-import") (part "CAPACITOR_?_060325V_10UF"))
    )
    (comp (ref "C8")
      (value "CAPACITOR_0603_10V_4.7NF")
      (footprint "eagle-import:0603-CAP")
      (fields
        (field (name "CAPACITANCE") "4.7nF")
        (field (name "MANUFACTURER") "Würth Elektronik")
        (field (name "MPN") "885012206012")
        (field (name "TOLERANCE") "10%")
        (field (name "VOLTAGE") "10V")
      )
      (libsource (lib "eagle-import") (part "CAPACITOR_?_060310V_4.7NF"))
    )
    (comp (ref "C100")
      (value "CAPACITOR_0603_10V_0.1UF")
      (footprint "eagle-import:0603-CAP")
      (fields
        (field (name "CAPACITANCE") "0.1µF")
        (field (name "MANUFACTURER") "Vishay Vitramon")
        (field (name "MPN") "VJ0603Y104JXQPW1BC")
        (field (name "TOLERANCE") "5%")
        (field (name "VOLTAGE") "10V")
      )
      (libsource (lib "eagle-import") (part "CAPACITOR_?_060310V_0.1UF"))
    )
    (comp (ref "C101")
      (value "CAPACITOR_0603_10V_0.1UF")
      (footprint "eagle-import:0603-CAP")
      (fields
        (field (name "CAPACITANCE") "0.1µF")
        (field (name "MANUFACTURER") "Vishay Vitramon")
        (field (name "MPN") "VJ0603Y104JXQPW1BC")
        (field (name "TOLERANCE") "5%")
        (field (name "VOLTAGE") "10V")
      )
      (libsource (lib "eagle-import") (part "CAPACITOR_?_060310V_0.1UF"))
    )
    (comp (ref "C102")
      (value "CAPACITOR_0603_10V_0.1UF")
      (footprint "eagle-import:0603-CAP")
      (fields
        (field (name "CAPACITANCE") "0.1µF")
        (field (name "MANUFACTURER") "Vishay Vitramon")
        (field (name "MPN") "VJ0603Y104JXQPW1BC")
        (field (name "TOLERANCE") "5%")
        (field (name "VOLTAGE") "10V")
      )
      (libsource (lib "eagle-import") (part "CAPACITOR_?_060310V_0.1UF"))
    )
    (comp (ref "C103")
      (value "CAPACITOR_0603_10V_0.1UF")
      (footprint "eagle-import:0603-CAP")
      (fields
        (field (name "CAPACITANCE") "0.1µF")
        (field (name "MANUFACTURER") "Vishay Vitramon")
        (field (name "MPN") "VJ0603Y104JXQPW1BC")
        (field (name "TOLERANCE") "5%")
        (field (name "VOLTAGE") "10V")
      )
      (libsource (lib "eagle-import") (part "CAPACITOR_?_060310V_0.1UF"))
    )
    (comp (ref "CAN_TERM")
      (value "JUMPER__1X02")
      (footprint "eagle-import:1X02")
      (fields (field (name "MANUFACTURER") "Molex") (field (name "MPN") "90120-1082 "))
      (libsource (lib "eagle-import") (part "JUMPER_?_1X02"))
    )
    (comp (ref "CHG_CAN")
      (value "CONNECTOR-6_MF_T_V_")
      (footprint "eagle-import:MOLEX_MICROFIT_PTH_VERTICAL_06_DUAL")
      (fields (field (name "MPN") "430450614") (field (name "MANUFACTURER") "MOLEX"))
      (libsource (lib "eagle-import") (part "CONNECTOR-6_?_MF_T_V"))
    )
    (comp (ref "D5")
      (value "TVS_15V")
      (footprint "eagle-import:SOT-23")
      (fields
        (field (name "MANUFACTURER") "Vishay General Semiconductor - Diodes Division")
        (field (name "MPN") "GSOT15-E3-08")
        (field (name "VOLTAGE") "15V")
      )
      (libsource (lib "eagle-import") (part "TVS_15V"))
    )
    (comp (ref "D100")
      (value "TVS_BIDIRECTIONAL_DUAL")
      (footprint "eagle-import:SC-70-3")
      (fields (field (name "MPN") "TPD2E007DCKR") (field (name "MANUFACTURER") "Texas Instruments"))
      (libsource (lib "eagle-import") (part "TVS_BIDIRECTIONAL_DUAL"))
    )
    (comp (ref "D101")
      (value "TVS_15V")
      (footprint "eagle-import:SOT-23")
      (fields
        (field (name "MANUFACTURER") "Vishay General Semiconductor - Diodes Division")
        (field (name "MPN") "GSOT15-E3-08")
        (field (name "VOLTAGE") "15V")
      )
      (libsource (lib "eagle-import") (part "TVS_15V"))
    )
    (comp (ref "D102")
      (value "TVS_15V")
      (footprint "eagle-import:SOT-23")
      (fields
        (field (name "MANUFACTURER") "Vishay General Semiconductor - Diodes Division")
        (field (name "MPN") "GSOT15-E3-08")
        (field (name "VOLTAGE") "15V")
      )
      (libsource (lib "eagle-import") (part "TVS_15V"))
    )
    (comp (ref "E_SELECT")
      (value "JUMPER_0603_")
      (footprint "eagle-import:0603-RES")
      (fields (field (name "MPN") "RC0603FR-130RL") (field (name "MANUFACTURER") "YAGEO"))
      (libsource (lib "eagle-import") (part "JUMPER_?_0603"))
    )
    (comp (ref "F_SELECT")
      (value "JUMPER_0603_")
      (footprint "eagle-import:0603-RES")
      (fields (field (name "MPN") "RC0603FR-130RL") (field (name "MANUFACTURER") "YAGEO"))
      (libsource (lib "eagle-import") (part "JUMPER_?_0603"))
    )
    (comp (ref "MAIN_CONNECTOR")
      (value "CONNECTOR-8_MF_T_V_")
      (footprint "eagle-import:MOLEX_MICROFIT_PTH_VERTICAL_08_DUAL")
      (fields (field (name "MPN") "430450814") (field (name "MANUFACTURER") "MOLEX"))
      (libsource (lib "eagle-import") (part "CONNECTOR-8_?_MF_T_V"))
    )
    (comp (ref "POWER")
      (value "CONNECTOR-2_μF_T_V_")
      (footprint "eagle-import:MOLEX_MICROFIT_PTH_VERTICAL_02_DUAL")
      (fields (field (name "MPN") "0430450227") (field (name "MANUFACTURER") "Molex"))
      (libsource (lib "eagle-import") (part "CONNECTOR-2_?_μF_T_V"))
    )
    (comp (ref "R27")
      (value "RESISTOR_0603_100K")
      (footprint "eagle-import:0603-RES")
      (fields
        (field (name "MANUFACTURER") "Yageo")
        (field (name "MPN") "RC0603FR-07100KL")
        (field (name "POWER") "0.1W")
        (field (name "RESISTANCE") "100k")
      )
      (libsource (lib "eagle-import") (part "RESISTOR_?_0603100K"))
    )
    (comp (ref "R28")
      (value "RESISTOR_0603_10K")
      (footprint "eagle-import:0603-RES")
      (fields
        (field (name "MANUFACTURER") "Yageo")
        (field (name "MPN") "RC0603FR-0710KL")
        (field (name "POWER") "0.1W")
        (field (name "RESISTANCE") "10k")
      )
      (libsource (lib "eagle-import") (part "RESISTOR_?_060310K"))
    )
    (comp (ref "R29")
      (value "RESISTOR_0603_10K")
      (footprint "eagle-import:0603-RES")
      (fields
        (field (name "MANUFACTURER") "Yageo")
        (field (name "MPN") "RC0603FR-0710KL")
        (field (name "POWER") "0.1W")
        (field (name "RESISTANCE") "10k")
      )
      (libsource (lib "eagle-import") (part "RESISTOR_?_060310K"))
    )
    (comp (ref "R30")
      (value "RESISTOR_0603_10K")
      (footprint "eagle-import:0603-RES")
      (fields
        (field (name "MANUFACTURER") "Yageo")
        (field (name "MPN") "RC0603FR-0710KL")
        (field (name "POWER") "0.1W")
        (field (name "RESISTANCE") "10k")
      )
      (libsource (lib "eagle-import") (part "RESISTOR_?_060310K"))
    )
    (comp (ref "R39")
      (value "RESISTOR_0603_60.4")
      (footprint "eagle-import:0603-RES")
      (fields
        (field (name "MANUFACTURER") "Yageo")
        (field (name "MPN") "RC0603FR-0760R4L")
        (field (name "POWER") "0.1W")
        (field (name "RESISTANCE") "60.4")
      )
      (libsource (lib "eagle-import") (part "RESISTOR_?_060360.4"))
    )
    (comp (ref "R40")
      (value "RESISTOR_0603_60.4")
      (footprint "eagle-import:0603-RES")
      (fields
        (field (name "MANUFACTURER") "Yageo")
        (field (name "MPN") "RC0603FR-0760R4L")
        (field (name "POWER") "0.1W")
        (field (name "RESISTANCE") "60.4")
      )
      (libsource (lib "eagle-import") (part "RESISTOR_?_060360.4"))
    )
    (comp (ref "R100")
      (value "RESISTOR_0603_240")
      (footprint "eagle-import:0603-RES")
      (fields
        (field (name "MANUFACTURER") "Yageo")
        (field (name "MPN") "RC0603FR-07240RL")
        (field (name "POWER") "0.1W")
        (field (name "RESISTANCE") "240")
      )
      (libsource (lib "eagle-import") (part "HyTechDevices_Jumper_RESISTOR_?_0603240"))
    )
    (comp (ref "U$100")
      (value "RELAY_SOLIDSTATE_NO")
      (footprint "eagle-import:DIP-4")
      (fields (field (name "MPN") "AQY214EHA") (field (name "MANUFACTURER") "AQY214EHA"))
      (libsource (lib "eagle-import") (part "RELAY_SOLIDSTATE_NO"))
    )
    (comp (ref "U1")
      (value "LOGICGATE_BUFFER")
      (footprint "eagle-import:SC-70-5")
      (fields (field (name "MANUFACTURER") "Texas Instruments"))
      (libsource (lib "eagle-import") (part "LOGICGATE_BUFFER"))
    )
    (comp (ref "U2")
      (value "ADM8316WBX30")
      (footprint "eagle-import:SOT-23-5")
      (fields (field (name "MANUFACTURER") "Analog Devices Inc.") (field (name "MPN") "ADM8316WBX30ARJZR7"))
      (libsource (lib "eagle-import") (part "ADM8316WBX30"))
    )
    (comp (ref "U3")
      (value "VOLTAGE_REGULATOR_SOT-223_5V")
      (footprint "eagle-import:SOT-223")
      (fields (field (name "MANUFACTURER") "STMicroelectronics") (field (name "MPN") "LDL1117S50R"))
      (libsource (lib "eagle-import") (part "VOLTAGE_REGULATOR_?_SOT-2235V"))
    )
    (comp (ref "U100")
      (value "MCP2562FD")
      (footprint "eagle-import:SOIC-08(NARROW,0.15_)")
      (fields (field (name "MPN") "MCP2562FD-E/SN") (field (name "MANUFACTURER") "Microchip Technology"))
      (libsource (lib "eagle-import") (part "MCP2562FD"))
    )
    (comp (ref "U101")
      (value "MCP2562FD")
      (footprint "eagle-import:SOIC-08(NARROW,0.15_)")
      (fields (field (name "MPN") "MCP2562FD-E/SN") (field (name "MANUFACTURER") "Microchip Technology"))
      (libsource (lib "eagle-import") (part "MCP2562FD"))
    )
    (comp (ref "XB1")
      (value "BATTERY_HOLDER_KEYSTONE_498")
      (footprint "eagle-import:498")
      (fields (field (name "MPN") "498") (field (name "MANUFACTURER") "Keystone Electronics"))
      (libsource (lib "eagle-import") (part "BATTERY_HOLDER_KEYSTONE_498"))
    )
    (comp (ref "XF1")
      (value "FUSE_HOLDER_MINIBLADEPTH")
      (footprint "eagle-import:3568")
      (fields (field (name "MANUFACTURER") "Keystone") (field (name "MPN") "3568"))
      (libsource (lib "eagle-import") (part "FUSE_HOLDER_PTHMINIBLADE"))
    )
    (comp (ref "XF2")
      (value "FUSE_HOLDER_MINIBLADEPTH")
      (footprint "eagle-import:3568")
      (fields (field (name "MANUFACTURER") "Keystone") (field (name "MPN") "3568"))
      (libsource (lib "eagle-import") (part "FUSE_HOLDER_PTHMINIBLADE"))
    )
  )
  (nets
    (net (code "1") (name "+5V") (class "Default")
      (node (ref "5V_PWR") (pin "2") (pinfunction "A_2") (pintype "passive"))
      (node (ref "A1") (pin "VIN") (pinfunction "VIN_VIN") (pintype "power_in"))
      (node (ref "A2") (pin "VIN") (pinfunction "VIN_VIN") (pintype "power_in"))
      (node (ref "C101") (pin "2") (pinfunction "2_2") (pintype "passive"))
      (node (ref "C103") (pin "2") (pinfunction "2_2") (pintype "passive"))
      (node (ref "C4") (pin "2") (pinfunction "2_2") (pintype "passive"))
      (node (ref "C5") (pin "1") (pinfunction "1_1") (pintype "passive"))
      (node (ref "C6") (pin "1") (pinfunction "1_1") (pintype "passive"))
      (node (ref "LATCH") (pin "2") (pinfunction "A_2") (pintype "passive"))
      (node (ref "TP12") (pin "1") (pinfunction "1_1") (pintype "passive"))
      (node (ref "U100") (pin "3") (pinfunction "VDD_3") (pintype "power_in"))
      (node (ref "U101") (pin "3") (pinfunction "VDD_3") (pintype "power_in"))
      (node (ref "U3") (pin "2") (pinfunction "OUT_2") (pintype "power_in"))
      (node (ref "U3") (pin "4") (pinfunction "OUT_4") (pintype "power_in"))
    )
    (net (code "2") (name "+12V") (class "Default")
      (node (ref "AUX_CAN") (pin "1") (pinfunction "+12V_1") (pintype "power_in"))
      (node (ref "C7") (pin "1") (pinfunction "1_1") (pintype "passive"))
      (node (ref "MAIN_CONNECTOR") (pin "4") (pinfunction "4_4") (pintype "passive"))
      (node (ref "R17") (pin "1") (pinfunction "1_1") (pintype "passive"))
      (node (ref "TP13") (pin "1") (pinfunction "1_1") (pintype "passive"))
      (node (ref "U$4") (pin "4") (pinfunction "CONTACT2_4") (pintype "bidirectional"))
      (node (ref "U3") (pin "3") (pinfunction "IN_3") (pintype "power_in"))
      (node (ref "XF1") (pin "3") (pinfunction "2_3") (pintype "passive"))
      (node (ref "XF1") (pin "4") (pinfunction "2_4") (pintype "passive"))
    )
    (net (code "3") (name "4.0_CRX") (class "Default")
      (node (ref "A2") (pin "D0") (pinfunction "(CRX1)D0_D0") (pintype "bidirectional"))
      (node (ref "A2") (pin "D4") (pinfunction "D4_D4") (pintype "bidirectional"))
      (node (ref "U100") (pin "4") (pinfunction "RXD_4") (pintype "output"))
    )
    (net (code "4") (name "4.0_CTX") (class "Default")
      (node (ref "A2") (pin "D1") (pinfunction "(CTX1)D1_D1") (pintype "bidirectional"))
      (node (ref "A2") (pin "D3") (pinfunction "D3_D3") (pintype "bidirectional"))
      (node (ref "U100") (pin "1") (pinfunction "TXD_1") (pintype "input"))
    )
    (net (code "5") (name "4.1_CRX") (class "Default")
      (node (ref "A1") (pin "D0") (pinfunction "(CRX1)D0_D0") (pintype "bidirectional"))
      (node (ref "A1") (pin "D4") (pinfunction "D4_D4") (pintype "bidirectional"))
      (node (ref "U101") (pin "4") (pinfunction "RXD_4") (pintype "output"))
    )
    (net (code "6") (name "4.1_CTX") (class "Default")
      (node (ref "A1") (pin "D1") (pinfunction "(CTX1)D1_D1") (pintype "bidirectional"))
      (node (ref "A1") (pin "D3") (pinfunction "D3_D3") (pintype "bidirectional"))
      (node (ref "U101") (pin "1") (pinfunction "TXD_1") (pintype "input"))
    )
    (net (code "7") (name "12V_READ") (class "Default")
      (node (ref "A1") (pin "D20") (pinfunction "A6_D20") (pintype "bidirectional"))
      (node (ref "A2") (pin "D20") (pinfunction "A6_D20") (pintype "bidirectional"))
      (node (ref "R10") (pin "1") (pinfunction "1_1") (pintype "passive"))
      (node (ref "R17") (pin "2") (pinfunction "2_2") (pintype "passive"))
    )
    (net (code "8") (name "BMS_OK") (class "Default")
      (node (ref "BMS_OK") (pin "2") (pinfunction "A_2") (pintype "passive"))
      (node (ref "D101") (pin "3") (pinfunction "C_3") (pintype "passive"))
      (node (ref "MAIN_CONNECTOR") (pin "6") (pinfunction "6_6") (pintype "passive"))
      (node (ref "R33") (pin "2") (pinfunction "2_2") (pintype "passive"))
      (node (ref "R34") (pin "2") (pinfunction "2_2") (pintype "passive"))
      (node (ref "TP7") (pin "1") (pinfunction "1_1") (pintype "passive"))
    )
    (net (code "9") (name "CANH") (class "Default")
      (node (ref "AUX_CAN") (pin "4") (pinfunction "CANH_4") (pintype "bidirectional"))
      (node (ref "CAN_TERM") (pin "2") (pinfunction "2_2") (pintype "passive"))
      (node (ref "CHG_CAN") (pin "4") (pinfunction "4_4") (pintype "passive"))
      (node (ref "D100") (pin "1") (pinfunction "C1_1") (pintype "passive"))
      (node (ref "MAIN_CONNECTOR") (pin "1") (pinfunction "1_1") (pintype "passive"))
      (node (ref "U100") (pin "7") (pinfunction "CANH_7") (pintype "bidirectional"))
      (node (ref "U101") (pin "7") (pinfunction "CANH_7") (pintype "bidirectional"))
    )
    (net (code "10") (name "CANL") (class "Default")
      (node (ref "AUX_CAN") (pin "3") (pinfunction "CANL_3") (pintype "bidirectional"))
      (node (ref "CHG_CAN") (pin "5") (pinfunction "5_5") (pintype "passive"))
      (node (ref "D100") (pin "2") (pinfunction "C2_2") (pintype "passive"))
      (node (ref "MAIN_CONNECTOR") (pin "2") (pinfunction "2_2") (pintype "passive"))
      (node (ref "R40") (pin "1") (pinfunction "1_1") (pintype "passive"))
      (node (ref "U100") (pin "6") (pinfunction "CANL_6") (pintype "bidirectional"))
      (node (ref "U101") (pin "6") (pinfunction "CANL_6") (pintype "bidirectional"))
    )
    (net (code "11") (name "CCU_OK") (class "Default")
      (node (ref "CCU_OK") (pin "2") (pinfunction "A_2") (pintype "passive"))
      (node (ref "R30") (pin "2") (pinfunction "2_2") (pintype "passive"))
      (node (ref "R31") (pin "2") (pinfunction "2_2") (pintype "passive"))
      (node (ref "TP9") (pin "1") (pinfunction "1_1") (pintype "passive"))
      (node (ref "U1") (pin "4") (pinfunction "OUT_4") (pintype "output"))
    )
    (net (code "12") (name "GND") (class "Default")
      (node (ref "A1") (pin "AGND/GND") (pinfunction "GND_AGND/GND") (pintype "bidirectional"))
      (node (ref "A1") (pin "GND") (pinfunction "GND_GND") (pintype "bidirectional"))
      (node (ref "A1") (pin "GND@2") (pinfunction "GND_GND@2") (pintype "bidirectional"))
      (node (ref "A2") (pin "AGND/GND") (pinfunction "GND_AGND/GND") (pintype "power_in"))
      (node (ref "A2") (pin "GND") (pinfunction "GND_GND") (pintype "power_in"))
      (node (ref "AUX_CAN") (pin "2") (pinfunction "GND_2") (pintype "power_in"))
      (node (ref "C1") (pin "1") (pinfunction "1_1") (pintype "passive"))
      (node (ref "C100") (pin "1") (pinfunction "1_1") (pintype "passive"))
      (node (ref "C101") (pin "1") (pinfunction "1_1") (pintype "passive"))
      (node (ref "C102") (pin "1") (pinfunction "1_1") (pintype "passive"))
      (node (ref "C103") (pin "1") (pinfunction "1_1") (pintype "passive"))
      (node (ref "C2") (pin "1") (pinfunction "1_1") (pintype "passive"))
      (node (ref "C3") (pin "1") (pinfunction "1_1") (pintype "passive"))
      (node (ref "C4") (pin "1") (pinfunction "1_1") (pintype "passive"))
      (node (ref "C5") (pin "2") (pinfunction "2_2") (pintype "passive"))
      (node (ref "C6") (pin "2") (pinfunction "2_2") (pintype "passive"))
      (node (ref "C7") (pin "2") (pinfunction "2_2") (pintype "passive"))
      (node (ref "C8") (pin "2") (pinfunction "2_2") (pintype "passive"))
      (node (ref "CHG_CAN") (pin "6") (pinfunction "6_6") (pintype "passive"))
      (node (ref "D100") (pin "3") (pinfunction "A_3") (pintype "passive"))
      (node (ref "D101") (pin "1") (pinfunction "A_1") (pintype "passive"))
      (node (ref "D102") (pin "1") (pinfunction "A_1") (pintype "passive"))
      (node (ref "D3") (pin "1") (pinfunction "C_1") (pintype "passive"))
      (node (ref "D5") (pin "1") (pinfunction "A_1") (pintype "passive"))
      (node (ref "K1") (pin "14") (pinfunction "4_14") (pintype "bidirectional"))
      (node (ref "K2") (pin "14") (pinfunction "4_14") (pintype "bidirectional"))
      (node (ref "K3") (pin "14") (pinfunction "4_14") (pintype "bidirectional"))
      (node (ref "LATCH_BUTTON") (pin "3") (pinfunction "S_3") (pintype "passive"))
      (node (ref "LATCH_BUTTON") (pin "4") (pinfunction "S_4") (pintype "passive"))
      (node (ref "MAIN_CONNECTOR") (pin "3") (pinfunction "3_3") (pintype "passive"))
      (node (ref "POWER") (pin "2") (pinfunction "2_2") (pintype "passive"))
      (node (ref "R1") (pin "2") (pinfunction "2_2") (pintype "passive"))
      (node (ref "R10") (pin "2") (pinfunction "2_2") (pintype "passive"))
      (node (ref "R11") (pin "2") (pinfunction "2_2") (pintype "passive"))
      (node (ref "R12") (pin "2") (pinfunction "2_2") (pintype "passive"))
      (node (ref "R13") (pin "2") (pinfunction "2_2") (pintype "passive"))
      (node (ref "R14") (pin "2") (pinfunction "2_2") (pintype "passive"))
      (node (ref "R15") (pin "2") (pinfunction "2_2") (pintype "passive"))
      (node (ref "R16") (pin "2") (pinfunction "2_2") (pintype "passive"))
      (node (ref "R2") (pin "2") (pinfunction "2_2") (pintype "passive"))
      (node (ref "R24") (pin "1") (pinfunction "1_1") (pintype "passive"))
      (node (ref "R26") (pin "2") (pinfunction "2_2") (pintype "passive"))
      (node (ref "R27") (pin "2") (pinfunction "2_2") (pintype "passive"))
      (node (ref "R28") (pin "2") (pinfunction "2_2") (pintype "passive"))
      (node (ref "R29") (pin "1") (pinfunction "1_1") (pintype "passive"))
      (node (ref "R30") (pin "1") (pinfunction "1_1") (pintype "passive"))
      (node (ref "R32") (pin "2") (pinfunction "2_2") (pintype "passive"))
      (node (ref "R33") (pin "1") (pinfunction "1_1") (pintype "passive"))
      (node (ref "R36") (pin "1") (pinfunction "1_1") (pintype "passive"))
      (node (ref "R7") (pin "2") (pinfunction "2_2") (pintype "passive"))
      (node (ref "R8") (pin "2") (pinfunction "2_2") (pintype "passive"))
      (node (ref "R9") (pin "2") (pinfunction "2_2") (pintype "passive"))
      (node (ref "SHDN_B") (pin "1") (pinfunction "C_1") (pintype "passive"))
      (node (ref "SHDN_C") (pin "1") (pinfunction "C_1") (pintype "passive"))
      (node (ref "SHDN_D") (pin "1") (pinfunction "C_1") (pintype "passive"))
      (node (ref "SHDN_E") (pin "1") (pinfunction "C_1") (pintype "passive"))
      (node (ref "TP1") (pin "1") (pinfunction "1_1") (pintype "passive"))
      (node (ref "U$100") (pin "2") (pinfunction "CONTROL-_2") (pintype "passive"))
      (node (ref "U$100") (pin "3") (pinfunction "CONTACT1_3") (pintype "bidirectional"))
      (node (ref "U$4") (pin "2") (pinfunction "CONTROL-_2") (pintype "passive"))
      (node (ref "U1") (pin "3") (pinfunction "GND_3") (pintype "power_in"))
      (node (ref "U100") (pin "2") (pinfunction "GND_2") (pintype "power_in"))
      (node (ref "U100") (pin "8") (pinfunction "STBY_8") (pintype "passive"))
      (node (ref "U101") (pin "2") (pinfunction "GND_2") (pintype "power_in"))
      (node (ref "U101") (pin "8") (pinfunction "STBY_8") (pintype "passive"))
      (node (ref "U2") (pin "2") (pinfunction "GND_2") (pintype "power_in"))
      (node (ref "U3") (pin "1") (pinfunction "GND_1") (pintype "power_in"))
      (node (ref "XB1") (pin "2") (pinfunction "MINUS_2") (pintype "power_in"))
    )
    (net (code "13") (name "IMD_OK") (class "Default")
      (node (ref "D102") (pin "3") (pinfunction "C_3") (pintype "passive"))
      (node (ref "MAIN_CONNECTOR") (pin "5") (pinfunction "5_5") (pintype "passive"))
      (node (ref "OKHS") (pin "2") (pinfunction "A_2") (pintype "passive"))
      (node (ref "R24") (pin "2") (pinfunction "2_2") (pintype "passive"))
      (node (ref "R25") (pin "2") (pinfunction "2_2") (pintype "passive"))
      (node (ref "TP8") (pin "1") (pinfunction "1_1") (pintype "passive"))
    )
    (net (code "14") (name "LATCH_BUTTON") (class "Default")
      (node (ref "D1") (pin "C") (pinfunction "C_C") (pintype "passive"))
      (node (ref "D2") (pin "C") (pinfunction "C_C") (pintype "passive"))
      (node (ref "D4") (pin "C") (pinfunction "C_C") (pintype "passive"))
      (node (ref "LATCH_BUTTON") (pin "1") (pinfunction "P_1") (pintype "passive"))
      (node (ref "LATCH_BUTTON") (pin "2") (pinfunction "P_2") (pintype "passive"))
      (node (ref "R35") (pin "2") (pinfunction "2_2") (pintype "passive"))
    )
    (net (code "15") (name "Net-(4.1_ONLY-Pad1)") (class "Default")
      (node (ref "4.1_ONLY") (pin "1") (pinfunction "1_1") (pintype "passive"))
      (node (ref "A1") (pin "3V3") (pinfunction "3.3V_3V3") (pintype "power_in"))
      (node (ref "A1") (pin "3V3@2") (pinfunction "3.3V_3V3@2") (pintype "power_in"))
      (node (ref "A1") (pin "3V3@3") (pinfunction "3.3V_3V3@3") (pintype "power_in"))
    )
    (net (code "16") (name "Net-(5V_PWR-C)") (class "Default")
      (node (ref "5V_PWR") (pin "1") (pinfunction "C_1") (pintype "passive"))
      (node (ref "R32") (pin "1") (pinfunction "1_1") (pintype "passive"))
    )
    (net (code "17") (name "Net-(BMS_OK-C)") (class "Default")
      (node (ref "BMS_OK") (pin "1") (pinfunction "C_1") (pintype "passive"))
      (node (ref "R2") (pin "1") (pinfunction "1_1") (pintype "passive"))
    )
    (net (code "18") (name "Net-(C8-Pad1)") (class "Default")
      (node (ref "C8") (pin "1") (pinfunction "1_1") (pintype "passive"))
      (node (ref "R39") (pin "1") (pinfunction "1_1") (pintype "passive"))
      (node (ref "R40") (pin "2") (pinfunction "2_2") (pintype "passive"))
    )
    (net (code "19") (name "Net-(CAN_TERM-Pad1)") (class "Default")
      (node (ref "CAN_TERM") (pin "1") (pinfunction "1_1") (pintype "passive"))
      (node (ref "R39") (pin "2") (pinfunction "2_2") (pintype "passive"))
    )
    (net (code "20") (name "Net-(CCU_OK-C)") (class "Default")
      (node (ref "CCU_OK") (pin "1") (pinfunction "C_1") (pintype "passive"))
      (node (ref "R9") (pin "1") (pinfunction "1_1") (pintype "passive"))
    )
    (net (code "21") (name "Net-(D3-A)") (class "Default")
      (node (ref "D3") (pin "2") (pinfunction "A_2") (pintype "passive"))
      (node (ref "R38") (pin "2") (pinfunction "2_2") (pintype "passive"))
    )
    (net (code "22") (name "Net-(D5-C)") (class "Default")
      (node (ref "D5") (pin "3") (pinfunction "C_3") (pintype "passive"))
      (node (ref "POWER") (pin "1") (pinfunction "1_1") (pintype "passive"))
      (node (ref "XF1") (pin "1") (pinfunction "1_1") (pintype "passive"))
      (node (ref "XF1") (pin "2") (pinfunction "1_2") (pintype "passive"))
      (node (ref "XF2") (pin "1") (pinfunction "1_1") (pintype "passive"))
      (node (ref "XF2") (pin "2") (pinfunction "1_2") (pintype "passive"))
    )
    (net (code "23") (name "Net-(E_SELECT-Pad2)") (class "Default")
      (node (ref "E_SELECT") (pin "2") (pinfunction "2_2") (pintype "passive"))
      (node (ref "F_SELECT") (pin "2") (pinfunction "2_2") (pintype "passive"))
      (node (ref "R100") (pin "1") (pinfunction "1_1") (pintype "passive"))
    )
    (net (code "24") (name "Net-(K1-3)") (class "Default")
      (node (ref "D1") (pin "A") (pinfunction "A_A") (pintype "passive"))
      (node (ref "D105") (pin "A") (pinfunction "A_A") (pintype "passive"))
      (node (ref "K1") (pin "11") (pinfunction "3_11") (pintype "bidirectional"))
      (node (ref "K1") (pin "A2") (pinfunction "COIL-_A2") (pintype "bidirectional"))
    )
    (net (code "25") (name "Net-(K1-COIL+)") (class "Default")
      (node (ref "D105") (pin "C") (pinfunction "C_C") (pintype "passive"))
      (node (ref "K1") (pin "A1") (pinfunction "COIL+_A1") (pintype "bidirectional"))
      (node (ref "R25") (pin "1") (pinfunction "1_1") (pintype "passive"))
    )
    (net (code "26") (name "Net-(K2-3)") (class "Default")
      (node (ref "D104") (pin "A") (pinfunction "A_A") (pintype "passive"))
      (node (ref "D2") (pin "A") (pinfunction "A_A") (pintype "passive"))
      (node (ref "K2") (pin "11") (pinfunction "3_11") (pintype "bidirectional"))
      (node (ref "K2") (pin "A2") (pinfunction "COIL-_A2") (pintype "bidirectional"))
    )
    (net (code "27") (name "Net-(K2-COIL+)") (class "Default")
      (node (ref "D104") (pin "C") (pinfunction "C_C") (pintype "passive"))
      (node (ref "K2") (pin "A1") (pinfunction "COIL+_A1") (pintype "bidirectional"))
      (node (ref "R34") (pin "1") (pinfunction "1_1") (pintype "passive"))
    )
    (net (code "28") (name "Net-(K3-3)") (class "Default")
      (node (ref "D103") (pin "A") (pinfunction "A_A") (pintype "passive"))
      (node (ref "D4") (pin "A") (pinfunction "A_A") (pintype "passive"))
      (node (ref "K3") (pin "11") (pinfunction "3_11") (pintype "bidirectional"))
      (node (ref "K3") (pin "A2") (pinfunction "COIL-_A2") (pintype "bidirectional"))
    )
    (net (code "29") (name "Net-(K3-COIL+)") (class "Default")
      (node (ref "D103") (pin "C") (pinfunction "C_C") (pintype "passive"))
      (node (ref "K3") (pin "A1") (pinfunction "COIL+_A1") (pintype "bidirectional"))
      (node (ref "R37") (pin "1") (pinfunction "1_1") (pintype "passive"))
    )
    (net (code "30") (name "Net-(LATCH-C)") (class "Default")
      (node (ref "LATCH") (pin "1") (pinfunction "C_1") (pintype "passive"))
      (node (ref "R35") (pin "1") (pinfunction "1_1") (pintype "passive"))
    )
    (net (code "31") (name "Net-(OKHS-C)") (class "Default")
      (node (ref "OKHS") (pin "1") (pinfunction "C_1") (pintype "passive"))
      (node (ref "R7") (pin "1") (pinfunction "1_1") (pintype "passive"))
    )
    (net (code "32") (name "Net-(SHDN_B-A)") (class "Default")
      (node (ref "R3") (pin "2") (pinfunction "2_2") (pintype "passive"))
      (node (ref "SHDN_B") (pin "2") (pinfunction "A_2") (pintype "passive"))
    )
    (net (code "33") (name "Net-(SHDN_C-A)") (class "Default")
      (node (ref "R4") (pin "2") (pinfunction "2_2") (pintype "passive"))
      (node (ref "SHDN_C") (pin "2") (pinfunction "A_2") (pintype "passive"))
    )
    (net (code "34") (name "Net-(SHDN_D-A)") (class "Default")
      (node (ref "R5") (pin "2") (pinfunction "2_2") (pintype "passive"))
      (node (ref "SHDN_D") (pin "2") (pinfunction "A_2") (pintype "passive"))
    )
    (net (code "35") (name "Net-(SHDN_E-A)") (class "Default")
      (node (ref "R6") (pin "2") (pinfunction "2_2") (pintype "passive"))
      (node (ref "SHDN_E") (pin "2") (pinfunction "A_2") (pintype "passive"))
    )
    (net (code "36") (name "Net-(SHDN_F-C)") (class "Default")
      (node (ref "R8") (pin "1") (pinfunction "1_1") (pintype "passive"))
      (node (ref "SHDN_F") (pin "1") (pinfunction "C_1") (pintype "passive"))
    )
    (net (code "37") (name "Net-(STATUS_4.0-C)") (class "Default")
      (node (ref "R26") (pin "1") (pinfunction "1_1") (pintype "passive"))
      (node (ref "STATUS_4.0") (pin "1") (pinfunction "C_1") (pintype "passive"))
    )
    (net (code "38") (name "Net-(STATUS_4.1-C)") (class "Default")
      (node (ref "R1") (pin "1") (pinfunction "1_1") (pintype "passive"))
      (node (ref "STATUS_4.1") (pin "1") (pinfunction "C_1") (pintype "passive"))
    )
    (net (code "39") (name "Net-(U$4-CONTACT1)") (class "Default")
      (node (ref "R36") (pin "2") (pinfunction "2_2") (pintype "passive"))
      (node (ref "R37") (pin "2") (pinfunction "2_2") (pintype "passive"))
      (node (ref "R38") (pin "1") (pinfunction "1_1") (pintype "passive"))
      (node (ref "U$4") (pin "3") (pinfunction "CONTACT1_3") (pintype "bidirectional"))
    )
    (net (code "40") (name "Net-(U$4-CONTROL+)") (class "Default")
      (node (ref "R31") (pin "1") (pinfunction "1_1") (pintype "passive"))
      (node (ref "U$4") (pin "1") (pinfunction "CONTROL+_1") (pintype "passive"))
    )
    (net (code "41") (name "Net-(U$100-CONTROL+)") (class "Default")
      (node (ref "R100") (pin "2") (pinfunction "2_2") (pintype "passive"))
      (node (ref "U$100") (pin "1") (pinfunction "CONTROL+_1") (pintype "passive"))
    )
    (net (code "42") (name "Net-(U1A-IN)") (class "Default")
      (node (ref "R27") (pin "1") (pinfunction "1_1") (pintype "passive"))
      (node (ref "U1") (pin "2") (pinfunction "IN_2") (pintype "input"))
      (node (ref "U2") (pin "1") (pinfunction "~{RESET}_1") (pintype "output"))
    )
    (net (code "43") (name "Net-(XB1-PLUS)") (class "Default")
      (node (ref "A1") (pin "VBAT") (pinfunction "VBAT_VBAT") (pintype "power_in"))
      (node (ref "XB1") (pin "1") (pinfunction "PLUS_1") (pintype "power_in"))
    )
    (net (code "44") (name "RPC_SWITCH") (class "Default")
      (node (ref "MAIN_CONNECTOR") (pin "8") (pinfunction "8_8") (pintype "passive"))
      (node (ref "U$100") (pin "4") (pinfunction "CONTACT2_4") (pintype "bidirectional"))
    )
    (net (code "45") (name "SHDN_A") (class "Default")
      (node (ref "K1") (pin "21") (pinfunction "6_21") (pintype "bidirectional"))
      (node (ref "R23") (pin "1") (pinfunction "1_1") (pintype "passive"))
      (node (ref "TP10") (pin "1") (pinfunction "1_1") (pintype "passive"))
      (node (ref "XF2") (pin "3") (pinfunction "2_3") (pintype "passive"))
      (node (ref "XF2") (pin "4") (pinfunction "2_4") (pintype "passive"))
    )
    (net (code "46") (name "SHDN_A_READ") (class "Default")
      (node (ref "A1") (pin "D14") (pinfunction "A0_D14") (pintype "bidirectional"))
      (node (ref "A2") (pin "D14") (pinfunction "A0_D14") (pintype "bidirectional"))
      (node (ref "R16") (pin "1") (pinfunction "1_1") (pintype "passive"))
      (node (ref "R23") (pin "2") (pinfunction "2_2") (pintype "passive"))
    )
    (net (code "47") (name "SHDN_B") (class "Default")
      (node (ref "K1") (pin "24") (pinfunction "5_24") (pintype "bidirectional"))
      (node (ref "K2") (pin "21") (pinfunction "6_21") (pintype "bidirectional"))
      (node (ref "R22") (pin "1") (pinfunction "1_1") (pintype "passive"))
      (node (ref "R3") (pin "1") (pinfunction "1_1") (pintype "passive"))
      (node (ref "TP2") (pin "1") (pinfunction "1_1") (pintype "passive"))
    )
    (net (code "48") (name "SHDN_B_READ") (class "Default")
      (node (ref "A1") (pin "D15") (pinfunction "A1_D15") (pintype "bidirectional"))
      (node (ref "A2") (pin "D15") (pinfunction "A1_D15") (pintype "bidirectional"))
      (node (ref "R15") (pin "1") (pinfunction "1_1") (pintype "passive"))
      (node (ref "R22") (pin "2") (pinfunction "2_2") (pintype "passive"))
    )
    (net (code "49") (name "SHDN_C") (class "Default")
      (node (ref "K2") (pin "24") (pinfunction "5_24") (pintype "bidirectional"))
      (node (ref "K3") (pin "21") (pinfunction "6_21") (pintype "bidirectional"))
      (node (ref "R21") (pin "1") (pinfunction "1_1") (pintype "passive"))
      (node (ref "R4") (pin "1") (pinfunction "1_1") (pintype "passive"))
      (node (ref "TP3") (pin "1") (pinfunction "1_1") (pintype "passive"))
    )
    (net (code "50") (name "SHDN_C_READ") (class "Default")
      (node (ref "A1") (pin "D16") (pinfunction "A2_D16") (pintype "bidirectional"))
      (node (ref "A2") (pin "D16") (pinfunction "A2_D16") (pintype "bidirectional"))
      (node (ref "R14") (pin "1") (pinfunction "1_1") (pintype "passive"))
      (node (ref "R21") (pin "2") (pinfunction "2_2") (pintype "passive"))
    )
    (net (code "51") (name "SHDN_D") (class "Default")
      (node (ref "K3") (pin "24") (pinfunction "5_24") (pintype "bidirectional"))
      (node (ref "R20") (pin "1") (pinfunction "1_1") (pintype "passive"))
      (node (ref "R5") (pin "1") (pinfunction "1_1") (pintype "passive"))
      (node (ref "SHDN_BTN") (pin "1") (pinfunction "1_1") (pintype "passive"))
      (node (ref "TP4") (pin "1") (pinfunction "1_1") (pintype "passive"))
    )
    (net (code "52") (name "SHDN_D_READ") (class "Default")
      (node (ref "A1") (pin "D17") (pinfunction "A3_D17") (pintype "bidirectional"))
      (node (ref "A2") (pin "D17") (pinfunction "A3_D17") (pintype "bidirectional"))
      (node (ref "R13") (pin "1") (pinfunction "1_1") (pintype "passive"))
      (node (ref "R20") (pin "2") (pinfunction "2_2") (pintype "passive"))
    )
    (net (code "53") (name "SHDN_E") (class "Default")
      (node (ref "CHG_CAN") (pin "3") (pinfunction "3_3") (pintype "passive"))
      (node (ref "E_SELECT") (pin "1") (pinfunction "1_1") (pintype "passive"))
      (node (ref "R19") (pin "1") (pinfunction "1_1") (pintype "passive"))
      (node (ref "R6") (pin "1") (pinfunction "1_1") (pintype "passive"))
      (node (ref "SHDN_BTN") (pin "2") (pinfunction "2_2") (pintype "passive"))
      (node (ref "TP5") (pin "1") (pinfunction "1_1") (pintype "passive"))
    )
    (net (code "54") (name "SHDN_E_READ") (class "Default")
      (node (ref "A1") (pin "D18") (pinfunction "A4_D18") (pintype "bidirectional"))
      (node (ref "A2") (pin "D18") (pinfunction "A4_D18") (pintype "bidirectional"))
      (node (ref "R12") (pin "1") (pinfunction "1_1") (pintype "passive"))
      (node (ref "R19") (pin "2") (pinfunction "2_2") (pintype "passive"))
    )
    (net (code "55") (name "SHDN_F") (class "Default")
      (node (ref "CHG_CAN") (pin "1") (pinfunction "1_1") (pintype "passive"))
      (node (ref "CHG_CAN") (pin "2") (pinfunction "2_2") (pintype "passive"))
      (node (ref "F_SELECT") (pin "1") (pinfunction "1_1") (pintype "passive"))
      (node (ref "MAIN_CONNECTOR") (pin "7") (pinfunction "7_7") (pintype "passive"))
      (node (ref "R18") (pin "1") (pinfunction "1_1") (pintype "passive"))
      (node (ref "SHDN_F") (pin "2") (pinfunction "A_2") (pintype "passive"))
      (node (ref "TP6") (pin "1") (pinfunction "1_1") (pintype "passive"))
    )
    (net (code "56") (name "SHDN_F_READ") (class "Default")
      (node (ref "A1") (pin "D19") (pinfunction "A5_D19") (pintype "bidirectional"))
      (node (ref "A2") (pin "D19") (pinfunction "A5_D19") (pintype "bidirectional"))
      (node (ref "R11") (pin "1") (pinfunction "1_1") (pintype "passive"))
      (node (ref "R18") (pin "2") (pinfunction "2_2") (pintype "passive"))
    )
    (net (code "57") (name "STATUS_4.0") (class "Default")
      (node (ref "A2") (pin "D5") (pinfunction "D5_D5") (pintype "bidirectional"))
      (node (ref "STATUS_4.0") (pin "2") (pinfunction "A_2") (pintype "passive"))
    )
    (net (code "58") (name "STATUS_4.1") (class "Default")
      (node (ref "A1") (pin "D5") (pinfunction "D5_D5") (pintype "bidirectional"))
      (node (ref "STATUS_4.1") (pin "2") (pinfunction "A_2") (pintype "passive"))
    )
    (net (code "59") (name "SW_SHUTDOWN") (class "Default")
      (node (ref "A1") (pin "D6") (pinfunction "D6_D6") (pintype "bidirectional"))
      (node (ref "A2") (pin "D6") (pinfunction "D6_D6") (pintype "bidirectional"))
      (node (ref "C1") (pin "2") (pinfunction "2_2") (pintype "passive"))
      (node (ref "R29") (pin "2") (pinfunction "2_2") (pintype "passive"))
      (node (ref "U2") (pin "3") (pinfunction "~{MR}_3") (pintype "input"))
    )
    (net (code "60") (name "VDD") (class "Default")
      (node (ref "4.1_ONLY") (pin "2") (pinfunction "2_2") (pintype "passive"))
      (node (ref "A2") (pin "3.3V") (pinfunction "3.3V_3.3V") (pintype "power_in"))
      (node (ref "C100") (pin "2") (pinfunction "2_2") (pintype "passive"))
      (node (ref "C102") (pin "2") (pinfunction "2_2") (pintype "passive"))
      (node (ref "C2") (pin "2") (pinfunction "2_2") (pintype "passive"))
      (node (ref "C3") (pin "2") (pinfunction "2_2") (pintype "passive"))
      (node (ref "TP11") (pin "1") (pinfunction "1_1") (pintype "passive"))
      (node (ref "U1") (pin "5") (pinfunction "VDD_5") (pintype "power_in"))
      (node (ref "U100") (pin "5") (pinfunction "VIO_5") (pintype "power_in"))
      (node (ref "U101") (pin "5") (pinfunction "VIO_5") (pintype "power_in"))
      (node (ref "U2") (pin "5") (pinfunction "VDD_5") (pintype "power_in"))
    )
    (net (code "61") (name "WATCHDOG_IN") (class "Default")
      (node (ref "A1") (pin "D7") (pinfunction "D7_D7") (pintype "bidirectional"))
      (node (ref "A2") (pin "D7") (pinfunction "D7_D7") (pintype "bidirectional"))
      (node (ref "R28") (pin "1") (pinfunction "1_1") (pintype "passive"))
      (node (ref "U2") (pin "4") (pinfunction "WDI_4") (pintype "input"))
    )
    (net (code "62") (name "unconnected-(A1-(CLK)D13-PadD13)") (class "Default")
      (node (ref "A1") (pin "D13") (pinfunction "(CLK)D13_D13") (pintype "bidirectional"))
    )
    (net (code "63") (name "unconnected-(A1-(CS)D10-PadD10)") (class "Default")
      (node (ref "A1") (pin "D10") (pinfunction "(CS)D10_D10") (pintype "bidirectional"))
    )
    (net (code "64") (name "unconnected-(A1-(SDI)D12-PadD12)") (class "Default")
      (node (ref "A1") (pin "D12") (pinfunction "(SDI)D12_D12") (pintype "bidirectional"))
    )
    (net (code "65") (name "unconnected-(A1-(SDO)D11-PadD11)") (class "Default")
      (node (ref "A1") (pin "D11") (pinfunction "(SDO)D11_D11") (pintype "bidirectional"))
    )
    (net (code "66") (name "unconnected-(A1-A7-PadD21)") (class "Default")
      (node (ref "A1") (pin "D21") (pinfunction "A7_D21") (pintype "bidirectional"))
    )
    (net (code "67") (name "unconnected-(A1-A8-PadD22)") (class "Default")
      (node (ref "A1") (pin "D22") (pinfunction "A8_D22") (pintype "bidirectional"))
    )
    (net (code "68") (name "unconnected-(A1-A9-PadD23)") (class "Default")
      (node (ref "A1") (pin "D23") (pinfunction "A9_D23") (pintype "bidirectional"))
    )
    (net (code "69") (name "unconnected-(A1-A10-PadD24)") (class "Default")
      (node (ref "A1") (pin "D24") (pinfunction "A10_D24") (pintype "bidirectional"))
    )
    (net (code "70") (name "unconnected-(A1-A11-PadD25)") (class "Default")
      (node (ref "A1") (pin "D25") (pinfunction "A11_D25") (pintype "bidirectional"))
    )
    (net (code "71") (name "unconnected-(A1-A12-PadD26)") (class "Default")
      (node (ref "A1") (pin "D26") (pinfunction "A12_D26") (pintype "bidirectional"))
    )
    (net (code "72") (name "unconnected-(A1-A13-PadD27)") (class "Default")
      (node (ref "A1") (pin "D27") (pinfunction "A13_D27") (pintype "bidirectional"))
    )
    (net (code "73") (name "unconnected-(A1-A14-PadD38)") (class "Default")
      (node (ref "A1") (pin "D38") (pinfunction "A14_D38") (pintype "bidirectional"))
    )
    (net (code "74") (name "unconnected-(A1-A15-PadD39)") (class "Default")
      (node (ref "A1") (pin "D39") (pinfunction "A15_D39") (pintype "bidirectional"))
    )
    (net (code "75") (name "unconnected-(A1-A16-PadD40)") (class "Default")
      (node (ref "A1") (pin "D40") (pinfunction "A16_D40") (pintype "bidirectional"))
    )
    (net (code "76") (name "unconnected-(A1-A17-PadD41)") (class "Default")
      (node (ref "A1") (pin "D41") (pinfunction "A17_D41") (pintype "bidirectional"))
    )
    (net (code "77") (name "unconnected-(A1-PadD2)") (class "Default")
      (node (ref "A1") (pin "D2") (pinfunction "D2_D2") (pintype "bidirectional"))
    )
    (net (code "78") (name "unconnected-(A1-PadD8)") (class "Default")
      (node (ref "A1") (pin "D8") (pinfunction "D8_D8") (pintype "bidirectional"))
    )
    (net (code "79") (name "unconnected-(A1-PadD9)") (class "Default")
      (node (ref "A1") (pin "D9") (pinfunction "D9_D9") (pintype "bidirectional"))
    )
    (net (code "80") (name "unconnected-(A1-PadD28)") (class "Default")
      (node (ref "A1") (pin "D28") (pinfunction "D28_D28") (pintype "bidirectional"))
    )
    (net (code "81") (name "unconnected-(A1-PadD29)") (class "Default")
      (node (ref "A1") (pin "D29") (pinfunction "D29_D29") (pintype "bidirectional"))
    )
    (net (code "82") (name "unconnected-(A1-PadD30)") (class "Default")
      (node (ref "A1") (pin "D30") (pinfunction "D30_D30") (pintype "bidirectional"))
    )
    (net (code "83") (name "unconnected-(A1-PadD31)") (class "Default")
      (node (ref "A1") (pin "D31") (pinfunction "D31_D31") (pintype "bidirectional"))
    )
    (net (code "84") (name "unconnected-(A1-PadD32)") (class "Default")
      (node (ref "A1") (pin "D32") (pinfunction "D32_D32") (pintype "bidirectional"))
    )
    (net (code "85") (name "unconnected-(A1-PadD33)") (class "Default")
      (node (ref "A1") (pin "D33") (pinfunction "D33_D33") (pintype "bidirectional"))
    )
    (net (code "86") (name "unconnected-(A1-PadD34)") (class "Default")
      (node (ref "A1") (pin "D34") (pinfunction "D34_D34") (pintype "bidirectional"))
    )
    (net (code "87") (name "unconnected-(A1-PadD35)") (class "Default")
      (node (ref "A1") (pin "D35") (pinfunction "D35_D35") (pintype "bidirectional"))
    )
    (net (code "88") (name "unconnected-(A1-PadD36)") (class "Default")
      (node (ref "A1") (pin "D36") (pinfunction "D36_D36") (pintype "bidirectional"))
    )
    (net (code "89") (name "unconnected-(A1-PadD37)") (class "Default")
      (node (ref "A1") (pin "D37") (pinfunction "D37_D37") (pintype "bidirectional"))
    )
    (net (code "90") (name "unconnected-(A2-(CLK)D13-PadD13)") (class "Default")
      (node (ref "A2") (pin "D13") (pinfunction "(CLK)D13_D13") (pintype "bidirectional"))
    )
    (net (code "91") (name "unconnected-(A2-(CS)D10-PadD10)") (class "Default")
      (node (ref "A2") (pin "D10") (pinfunction "(CS)D10_D10") (pintype "bidirectional"))
    )
    (net (code "92") (name "unconnected-(A2-(SDI)D12-PadD12)") (class "Default")
      (node (ref "A2") (pin "D12") (pinfunction "(SDI)D12_D12") (pintype "bidirectional"))
    )
    (net (code "93") (name "unconnected-(A2-(SDO)D11-PadD11)") (class "Default")
      (node (ref "A2") (pin "D11") (pinfunction "(SDO)D11_D11") (pintype "bidirectional"))
    )
    (net (code "94") (name "unconnected-(A2-A7-PadD21)") (class "Default")
      (node (ref "A2") (pin "D21") (pinfunction "A7_D21") (pintype "bidirectional"))
    )
    (net (code "95") (name "unconnected-(A2-A8-PadD22)") (class "Default")
      (node (ref "A2") (pin "D22") (pinfunction "A8_D22") (pintype "bidirectional"))
    )
    (net (code "96") (name "unconnected-(A2-A9-PadD23)") (class "Default")
      (node (ref "A2") (pin "D23") (pinfunction "A9_D23") (pintype "bidirectional"))
    )
    (net (code "97") (name "unconnected-(A2-PadD2)") (class "Default")
      (node (ref "A2") (pin "D2") (pinfunction "D2_D2") (pintype "bidirectional"))
    )
    (net (code "98") (name "unconnected-(A2-PadD8)") (class "Default")
      (node (ref "A2") (pin "D8") (pinfunction "D8_D8") (pintype "bidirectional"))
    )
    (net (code "99") (name "unconnected-(A2-PadD9)") (class "Default")
      (node (ref "A2") (pin "D9") (pinfunction "D9_D9") (pintype "bidirectional"))
    )
    (net (code "100") (name "unconnected-(K1-2-Pad12)") (class "Default")
      (node (ref "K1") (pin "12") (pinfunction "2_12") (pintype "bidirectional"))
    )
    (net (code "101") (name "unconnected-(K1-7-Pad22)") (class "Default")
      (node (ref "K1") (pin "22") (pinfunction "7_22") (pintype "bidirectional"))
    )
    (net (code "102") (name "unconnected-(K2-2-Pad12)") (class "Default")
      (node (ref "K2") (pin "12") (pinfunction "2_12") (pintype "bidirectional"))
    )
    (net (code "103") (name "unconnected-(K2-7-Pad22)") (class "Default")
      (node (ref "K2") (pin "22") (pinfunction "7_22") (pintype "bidirectional"))
    )
    (net (code "104") (name "unconnected-(K3-2-Pad12)") (class "Default")
      (node (ref "K3") (pin "12") (pinfunction "2_12") (pintype "bidirectional"))
    )
    (net (code "105") (name "unconnected-(K3-7-Pad22)") (class "Default")
      (node (ref "K3") (pin "22") (pinfunction "7_22") (pintype "bidirectional"))
    )
  )
)
